# dualHYD-PRESS.net
KiCad netlist of a schematic drawn in EAGLE
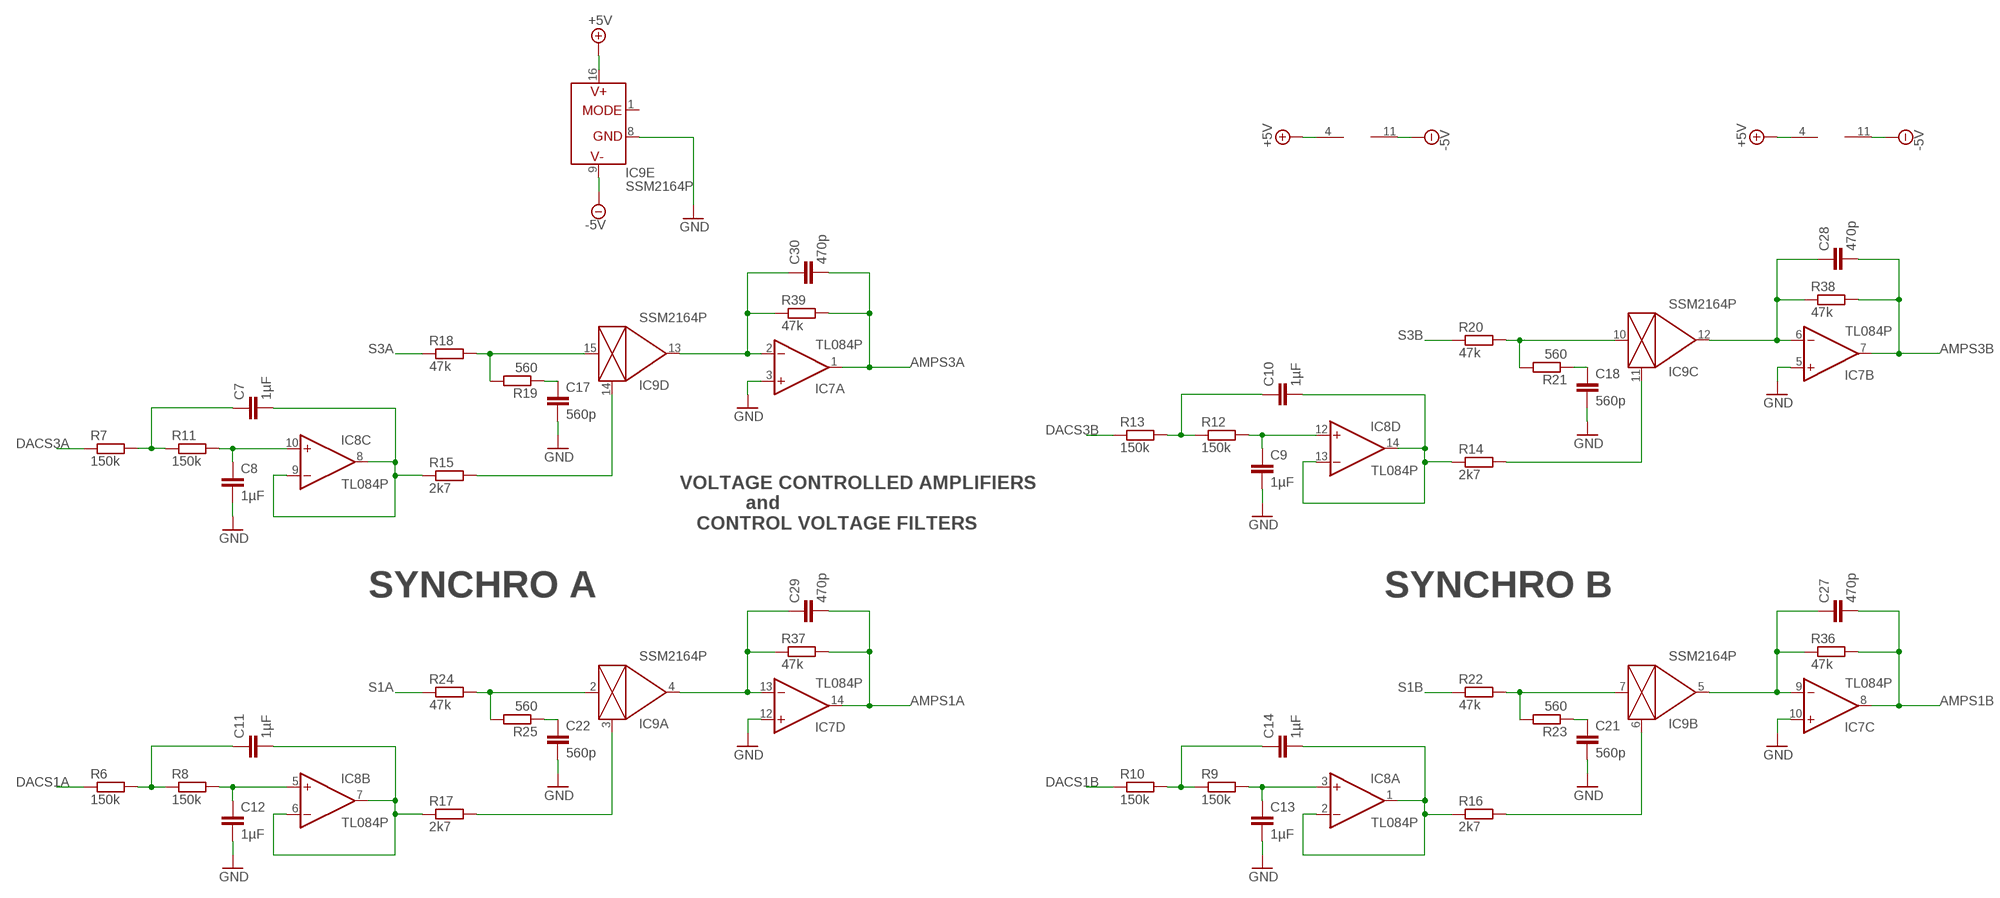
[diagram p0: schematic, sheet 1]
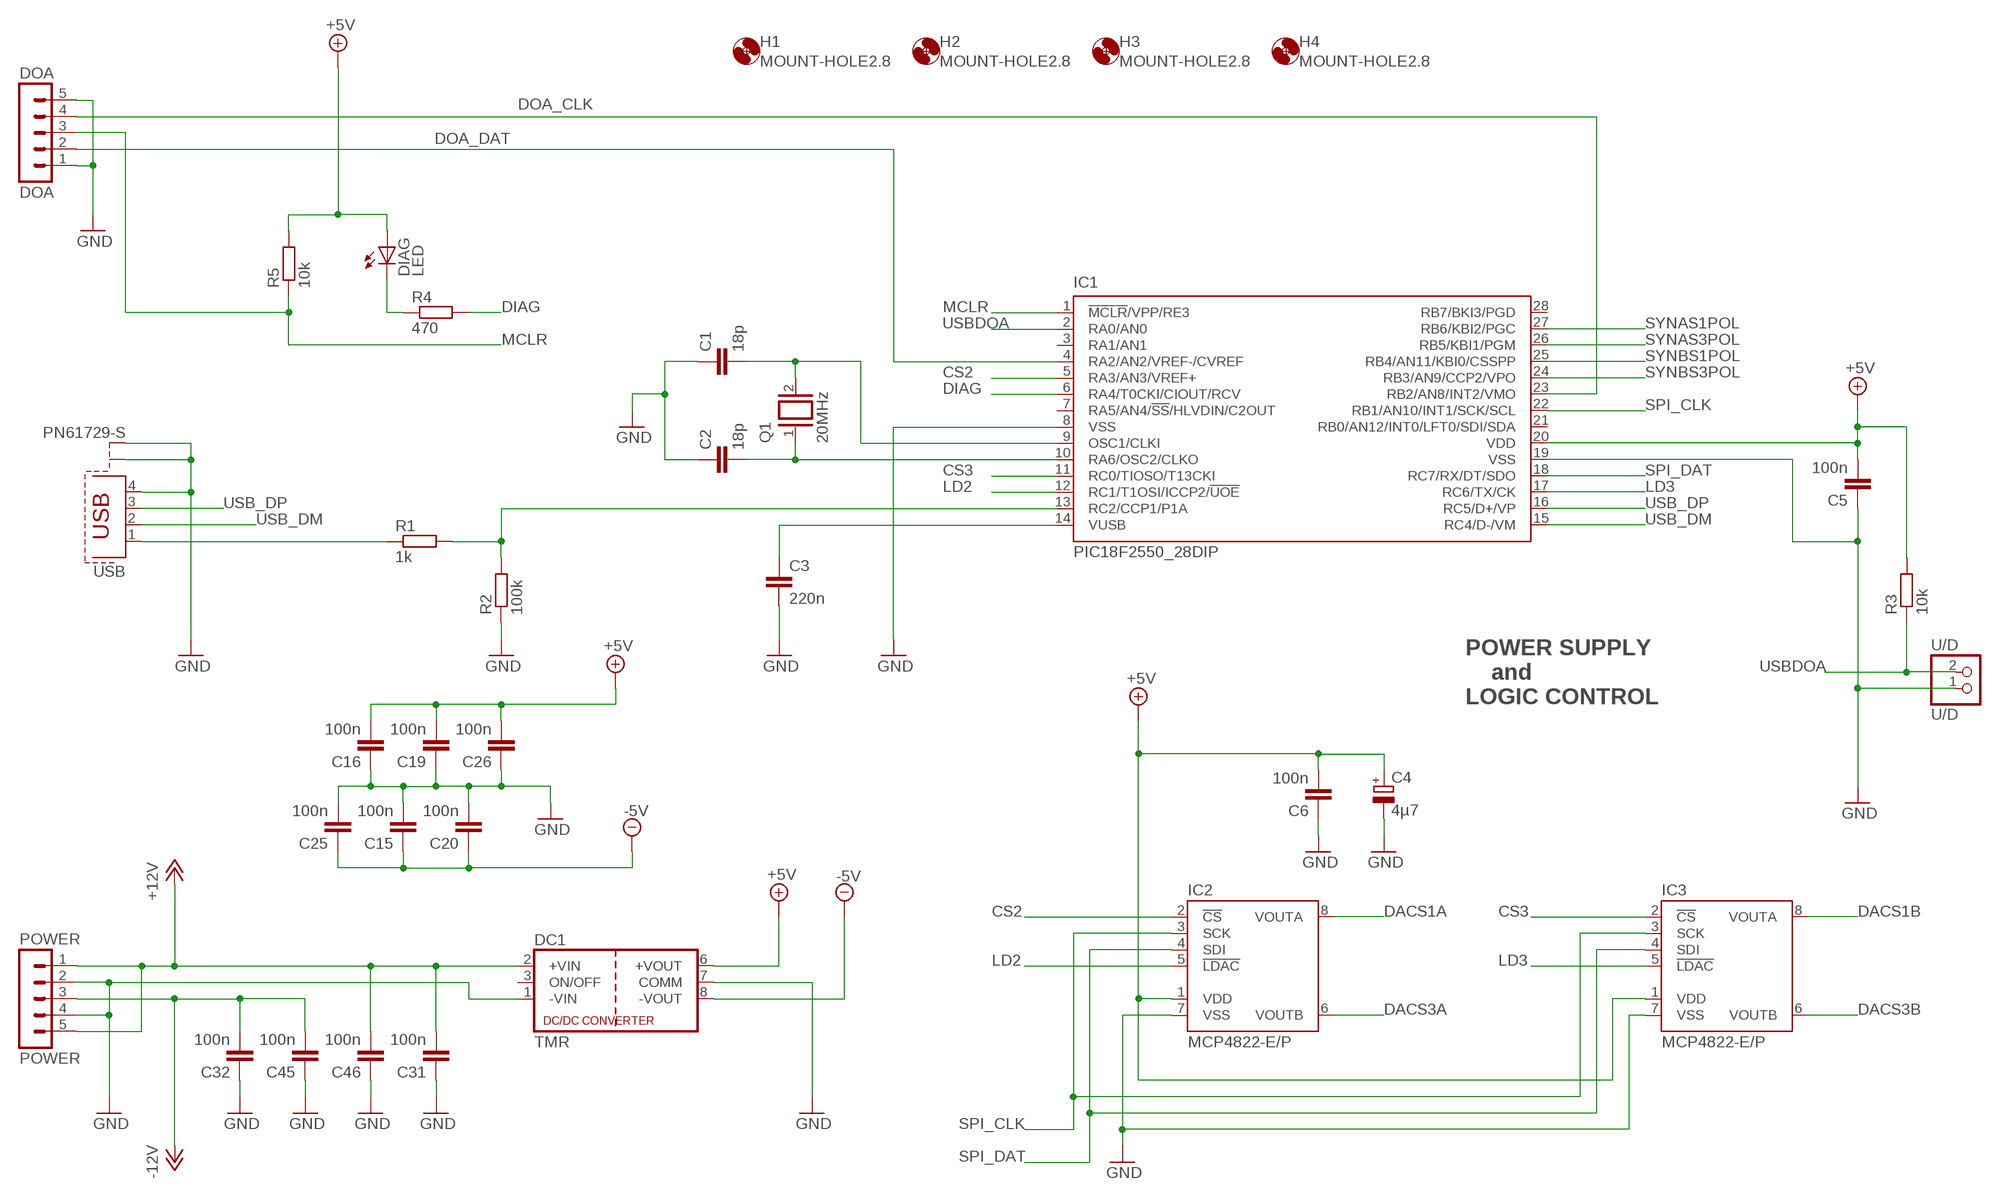
[diagram p1: schematic, sheet 2]
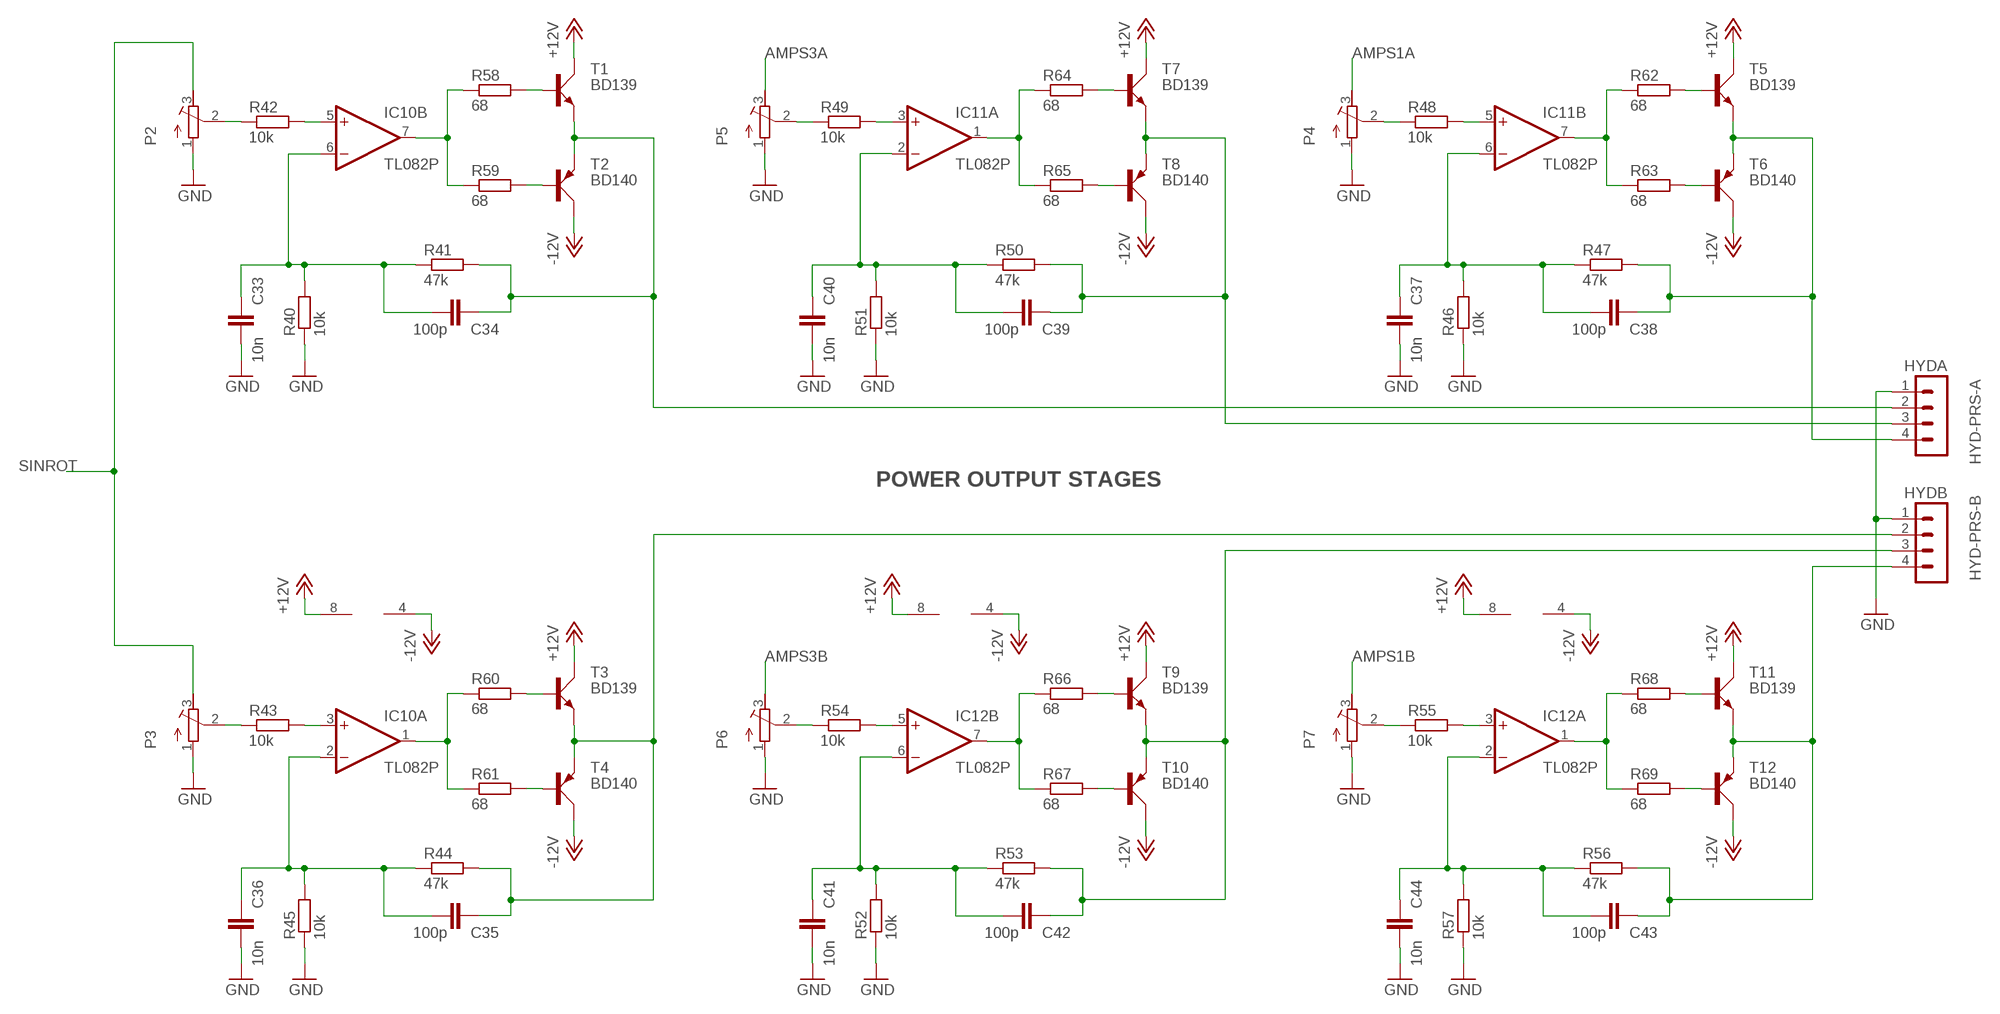
[diagram p2: schematic, sheet 3]
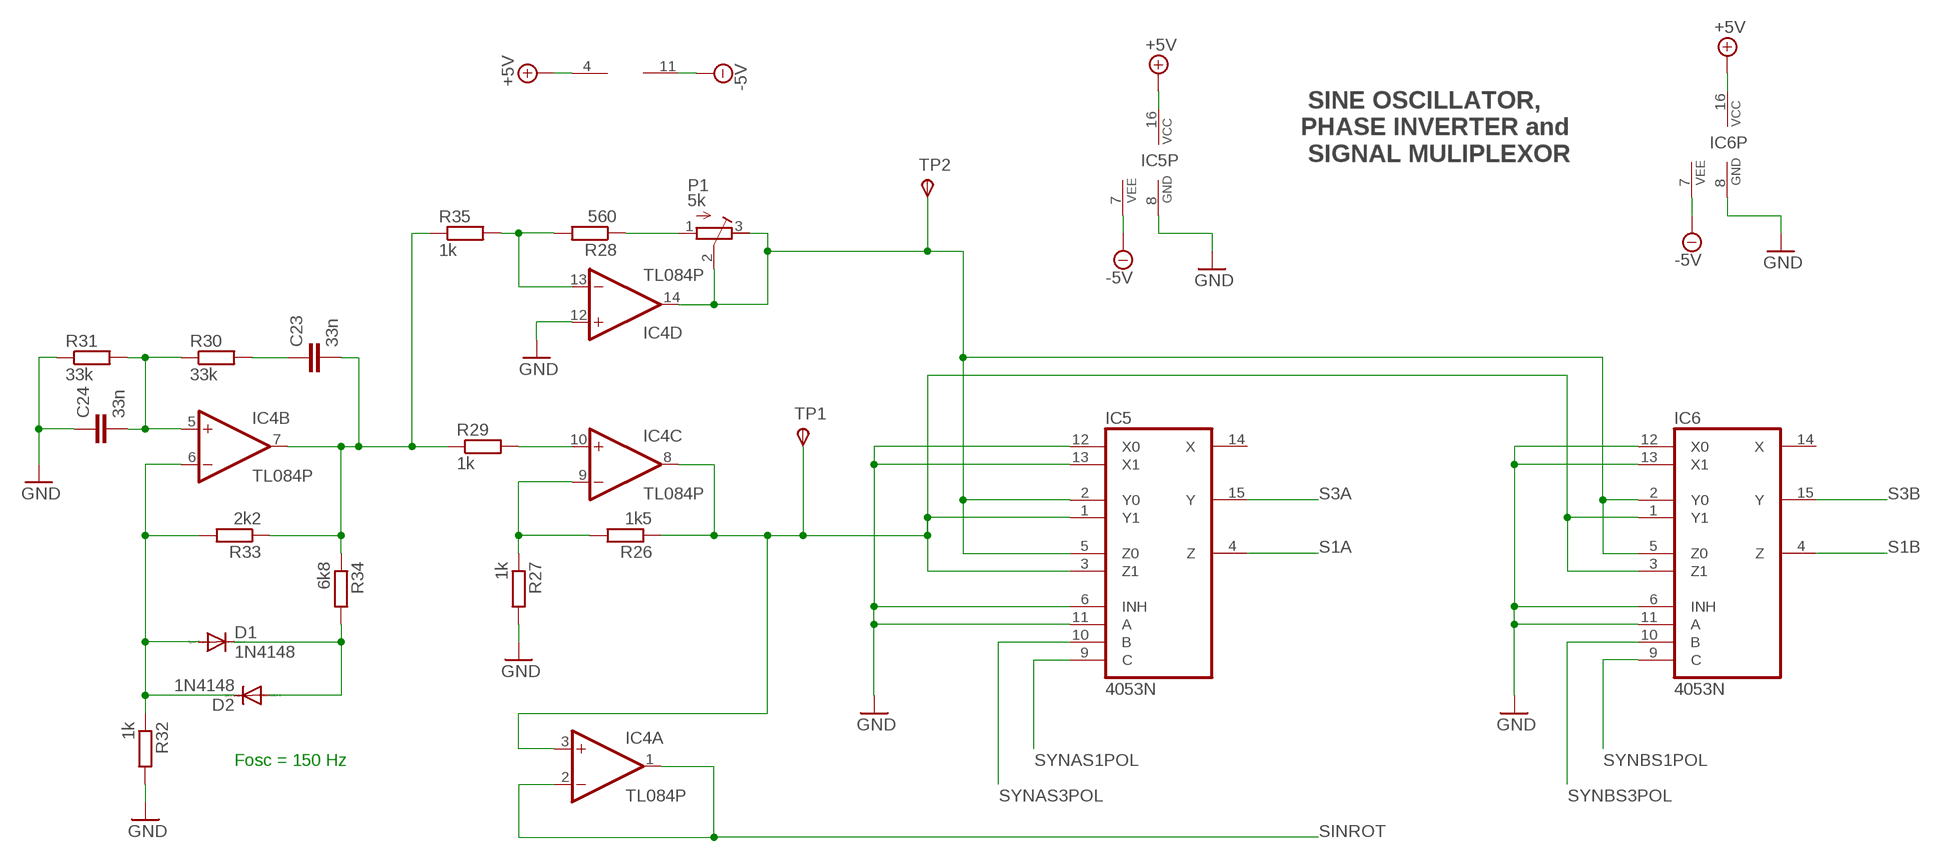
[diagram p3: schematic, sheet 4]

(export (version "E")
  (design (tool "Eeschema 10.0.6"))
  (components
    (comp (ref "C7")
      (value "1µF")
      (footprint "eagle-import:C025-025X050")
      (libsource (lib "eagle-import") (part "C-EU025-025X050"))
    )
    (comp (ref "C8")
      (value "1µF")
      (footprint "eagle-import:C025-025X050")
      (libsource (lib "eagle-import") (part "C-EU025-025X050"))
    )
    (comp (ref "C9")
      (value "1µF")
      (footprint "eagle-import:C025-025X050")
      (libsource (lib "eagle-import") (part "C-EU025-025X050"))
    )
    (comp (ref "C10")
      (value "1µF")
      (footprint "eagle-import:C025-025X050")
      (libsource (lib "eagle-import") (part "C-EU025-025X050"))
    )
    (comp (ref "C11")
      (value "1µF")
      (footprint "eagle-import:C025-025X050")
      (libsource (lib "eagle-import") (part "C-EU025-025X050"))
    )
    (comp (ref "C12")
      (value "1µF")
      (footprint "eagle-import:C025-025X050")
      (libsource (lib "eagle-import") (part "C-EU025-025X050"))
    )
    (comp (ref "C13")
      (value "1µF")
      (footprint "eagle-import:C025-025X050")
      (libsource (lib "eagle-import") (part "C-EU025-025X050"))
    )
    (comp (ref "C14")
      (value "1µF")
      (footprint "eagle-import:C025-025X050")
      (libsource (lib "eagle-import") (part "C-EU025-025X050"))
    )
    (comp (ref "C17")
      (value "560p")
      (footprint "eagle-import:C025-025X050")
      (libsource (lib "eagle-import") (part "C-EU025-025X050"))
    )
    (comp (ref "C18")
      (value "560p")
      (footprint "eagle-import:C025-025X050")
      (libsource (lib "eagle-import") (part "C-EU025-025X050"))
    )
    (comp (ref "C21")
      (value "560p")
      (footprint "eagle-import:C025-025X050")
      (libsource (lib "eagle-import") (part "C-EU025-025X050"))
    )
    (comp (ref "C22")
      (value "560p")
      (footprint "eagle-import:C025-025X050")
      (libsource (lib "eagle-import") (part "C-EU025-025X050"))
    )
    (comp (ref "C27")
      (value "470p")
      (footprint "eagle-import:C025-025X050")
      (libsource (lib "eagle-import") (part "C-EU025-025X050"))
    )
    (comp (ref "C28")
      (value "470p")
      (footprint "eagle-import:C025-025X050")
      (libsource (lib "eagle-import") (part "C-EU025-025X050"))
    )
    (comp (ref "C29")
      (value "470p")
      (footprint "eagle-import:C025-025X050")
      (libsource (lib "eagle-import") (part "C-EU025-025X050"))
    )
    (comp (ref "C30")
      (value "470p")
      (footprint "eagle-import:C025-025X050")
      (libsource (lib "eagle-import") (part "C-EU025-025X050"))
    )
    (comp (ref "IC7")
      (value "TL084P")
      (footprint "eagle-import:DIL14")
      (libsource (lib "eagle-import") (part "TL084P"))
    )
    (comp (ref "IC8")
      (value "TL084P")
      (footprint "eagle-import:DIL14")
      (libsource (lib "eagle-import") (part "TL084P"))
    )
    (comp (ref "IC9")
      (value "SSM2164P")
      (footprint "eagle-import:DIL16")
      (libsource (lib "eagle-import") (part "SSM2164P"))
    )
    (comp (ref "R6")
      (value "150k")
      (footprint "eagle-import:0207_7")
      (libsource (lib "eagle-import") (part "R-EU_0207/7"))
    )
    (comp (ref "R7")
      (value "150k")
      (footprint "eagle-import:0207_7")
      (libsource (lib "eagle-import") (part "R-EU_0207/7"))
    )
    (comp (ref "R8")
      (value "150k")
      (footprint "eagle-import:0207_7")
      (libsource (lib "eagle-import") (part "R-EU_0207/7"))
    )
    (comp (ref "R9")
      (value "150k")
      (footprint "eagle-import:0207_7")
      (libsource (lib "eagle-import") (part "R-EU_0207/7"))
    )
    (comp (ref "R10")
      (value "150k")
      (footprint "eagle-import:0207_7")
      (libsource (lib "eagle-import") (part "R-EU_0207/7"))
    )
    (comp (ref "R11")
      (value "150k")
      (footprint "eagle-import:0207_7")
      (libsource (lib "eagle-import") (part "R-EU_0207/7"))
    )
    (comp (ref "R12")
      (value "150k")
      (footprint "eagle-import:0207_7")
      (libsource (lib "eagle-import") (part "R-EU_0207/7"))
    )
    (comp (ref "R13")
      (value "150k")
      (footprint "eagle-import:0207_7")
      (libsource (lib "eagle-import") (part "R-EU_0207/7"))
    )
    (comp (ref "R14")
      (value "2k7")
      (footprint "eagle-import:0207_7")
      (libsource (lib "eagle-import") (part "R-EU_0207/7"))
    )
    (comp (ref "R15")
      (value "2k7")
      (footprint "eagle-import:0207_7")
      (libsource (lib "eagle-import") (part "R-EU_0207/7"))
    )
    (comp (ref "R16")
      (value "2k7")
      (footprint "eagle-import:0207_7")
      (libsource (lib "eagle-import") (part "R-EU_0207/7"))
    )
    (comp (ref "R17")
      (value "2k7")
      (footprint "eagle-import:0207_7")
      (libsource (lib "eagle-import") (part "R-EU_0207/7"))
    )
    (comp (ref "R18")
      (value "47k")
      (footprint "eagle-import:0207_7")
      (libsource (lib "eagle-import") (part "R-EU_0207/7"))
    )
    (comp (ref "R19")
      (value "560")
      (footprint "eagle-import:0207_7")
      (libsource (lib "eagle-import") (part "R-EU_0207/7"))
    )
    (comp (ref "R20")
      (value "47k")
      (footprint "eagle-import:0207_7")
      (libsource (lib "eagle-import") (part "R-EU_0207/7"))
    )
    (comp (ref "R21")
      (value "560")
      (footprint "eagle-import:0207_7")
      (libsource (lib "eagle-import") (part "R-EU_0207/7"))
    )
    (comp (ref "R22")
      (value "47k")
      (footprint "eagle-import:0207_7")
      (libsource (lib "eagle-import") (part "R-EU_0207/7"))
    )
    (comp (ref "R23")
      (value "560")
      (footprint "eagle-import:0207_7")
      (libsource (lib "eagle-import") (part "R-EU_0207/7"))
    )
    (comp (ref "R24")
      (value "47k")
      (footprint "eagle-import:0207_7")
      (libsource (lib "eagle-import") (part "R-EU_0207/7"))
    )
    (comp (ref "R25")
      (value "560")
      (footprint "eagle-import:0207_7")
      (libsource (lib "eagle-import") (part "R-EU_0207/7"))
    )
    (comp (ref "R36")
      (value "47k")
      (footprint "eagle-import:0207_7")
      (libsource (lib "eagle-import") (part "R-EU_0207/7"))
    )
    (comp (ref "R37")
      (value "47k")
      (footprint "eagle-import:0207_7")
      (libsource (lib "eagle-import") (part "R-EU_0207/7"))
    )
    (comp (ref "R38")
      (value "47k")
      (footprint "eagle-import:0207_7")
      (libsource (lib "eagle-import") (part "R-EU_0207/7"))
    )
    (comp (ref "R39")
      (value "47k")
      (footprint "eagle-import:0207_7")
      (libsource (lib "eagle-import") (part "R-EU_0207/7"))
    )
    (comp (ref "C23")
      (value "33n")
      (footprint "eagle-import:C025-024X044")
      (libsource (lib "eagle-import") (part "C-EU025-024X044"))
    )
    (comp (ref "C24")
      (value "33n")
      (footprint "eagle-import:C025-024X044")
      (libsource (lib "eagle-import") (part "C-EU025-024X044"))
    )
    (comp (ref "D1")
      (value "1N4148")
      (footprint "eagle-import:DO35-7")
      (libsource (lib "eagle-import") (part "1N4148DO35-7"))
    )
    (comp (ref "D2")
      (value "1N4148")
      (footprint "eagle-import:DO35-7")
      (libsource (lib "eagle-import") (part "1N4148DO35-7"))
    )
    (comp (ref "IC4")
      (value "TL084P")
      (footprint "eagle-import:DIL14")
      (libsource (lib "eagle-import") (part "TL084P"))
    )
    (comp (ref "IC5")
      (value "4053N")
      (footprint "eagle-import:DIL16")
      (libsource (lib "eagle-import") (part "4053N"))
    )
    (comp (ref "IC6")
      (value "4053N")
      (footprint "eagle-import:DIL16")
      (libsource (lib "eagle-import") (part "4053N"))
    )
    (comp (ref "P1")
      (value "5k")
      (footprint "eagle-import:RTRIM64Y")
      (libsource (lib "eagle-import") (part "R-TRIMM64Y"))
    )
    (comp (ref "R26")
      (value "1k5")
      (footprint "eagle-import:0204_7")
      (libsource (lib "eagle-import") (part "R-EU_0204/7"))
    )
    (comp (ref "R27")
      (value "1k")
      (footprint "eagle-import:0204_7")
      (libsource (lib "eagle-import") (part "R-EU_0204/7"))
    )
    (comp (ref "R28")
      (value "560")
      (footprint "eagle-import:0204_7")
      (libsource (lib "eagle-import") (part "R-EU_0204/7"))
    )
    (comp (ref "R29")
      (value "1k")
      (footprint "eagle-import:0204_7")
      (libsource (lib "eagle-import") (part "R-EU_0204/7"))
    )
    (comp (ref "R30")
      (value "33k")
      (footprint "eagle-import:0204_7")
      (libsource (lib "eagle-import") (part "R-EU_0204/7"))
    )
    (comp (ref "R31")
      (value "33k")
      (footprint "eagle-import:0204_7")
      (libsource (lib "eagle-import") (part "R-EU_0204/7"))
    )
    (comp (ref "R32")
      (value "1k")
      (footprint "eagle-import:0204_7")
      (libsource (lib "eagle-import") (part "R-EU_0204/7"))
    )
    (comp (ref "R33")
      (value "2k2")
      (footprint "eagle-import:0204_7")
      (libsource (lib "eagle-import") (part "R-EU_0204/7"))
    )
    (comp (ref "R34")
      (value "6k8")
      (footprint "eagle-import:0204_7")
      (libsource (lib "eagle-import") (part "R-EU_0204/7"))
    )
    (comp (ref "R35")
      (value "1k")
      (footprint "eagle-import:0204_7")
      (libsource (lib "eagle-import") (part "R-EU_0204/7"))
    )
    (comp (ref "TP1")
      (value "TPSPAD1-17")
      (footprint "eagle-import:P1-17")
      (libsource (lib "eagle-import") (part "TPSPAD1-17"))
    )
    (comp (ref "TP2")
      (value "TPSPAD1-17")
      (footprint "eagle-import:P1-17")
      (libsource (lib "eagle-import") (part "TPSPAD1-17"))
    )
    (comp (ref "C1")
      (value "18p")
      (footprint "eagle-import:C025-025X050")
      (libsource (lib "eagle-import") (part "C-EU025-025X050"))
    )
    (comp (ref "C2")
      (value "18p")
      (footprint "eagle-import:C025-025X050")
      (libsource (lib "eagle-import") (part "C-EU025-025X050"))
    )
    (comp (ref "C3")
      (value "220n")
      (footprint "eagle-import:C5B3")
      (libsource (lib "eagle-import") (part "C5/3"))
    )
    (comp (ref "C4")
      (value "4µ7")
      (footprint "eagle-import:E2,5-5")
      (libsource (lib "eagle-import") (part "CPOL-EUE2.5-5"))
    )
    (comp (ref "C5")
      (value "100n")
      (footprint "eagle-import:C025-025X050")
      (libsource (lib "eagle-import") (part "C-EU025-025X050"))
    )
    (comp (ref "C6")
      (value "100n")
      (footprint "eagle-import:C025-025X050")
      (libsource (lib "eagle-import") (part "C-EU025-025X050"))
    )
    (comp (ref "C15")
      (value "100n")
      (footprint "eagle-import:C025-025X050")
      (libsource (lib "eagle-import") (part "C-EU025-025X050"))
    )
    (comp (ref "C16")
      (value "100n")
      (footprint "eagle-import:C025-025X050")
      (libsource (lib "eagle-import") (part "C-EU025-025X050"))
    )
    (comp (ref "C19")
      (value "100n")
      (footprint "eagle-import:C025-025X050")
      (libsource (lib "eagle-import") (part "C-EU025-025X050"))
    )
    (comp (ref "C20")
      (value "100n")
      (footprint "eagle-import:C025-025X050")
      (libsource (lib "eagle-import") (part "C-EU025-025X050"))
    )
    (comp (ref "C25")
      (value "100n")
      (footprint "eagle-import:C025-025X050")
      (libsource (lib "eagle-import") (part "C-EU025-025X050"))
    )
    (comp (ref "C26")
      (value "100n")
      (footprint "eagle-import:C025-025X050")
      (libsource (lib "eagle-import") (part "C-EU025-025X050"))
    )
    (comp (ref "C31")
      (value "100n")
      (footprint "eagle-import:C025-025X050")
      (libsource (lib "eagle-import") (part "C-EU025-025X050"))
    )
    (comp (ref "C32")
      (value "100n")
      (footprint "eagle-import:C025-025X050")
      (libsource (lib "eagle-import") (part "C-EU025-025X050"))
    )
    (comp (ref "C45")
      (value "100n")
      (footprint "eagle-import:C025-025X050")
      (libsource (lib "eagle-import") (part "C-EU025-025X050"))
    )
    (comp (ref "C46")
      (value "100n")
      (footprint "eagle-import:C025-025X050")
      (libsource (lib "eagle-import") (part "C-EU025-025X050"))
    )
    (comp (ref "DC1")
      (value "TMR")
      (footprint "eagle-import:TRACO_SIP-8")
      (libsource (lib "eagle-import") (part "TMR"))
    )
    (comp (ref "DIAG")
      (value "LED")
      (footprint "eagle-import:LED3MM")
      (libsource (lib "eagle-import") (part "LED3MM"))
    )
    (comp (ref "DOA")
      (value "DOA")
      (footprint "eagle-import:MA05-1")
      (libsource (lib "eagle-import") (part "MA05-1"))
    )
    (comp (ref "H1")
      (value "MOUNT-HOLE2.8")
      (footprint "eagle-import:2,8")
      (libsource (lib "eagle-import") (part "MOUNT-HOLE2.8"))
    )
    (comp (ref "H2")
      (value "MOUNT-HOLE2.8")
      (footprint "eagle-import:2,8")
      (libsource (lib "eagle-import") (part "MOUNT-HOLE2.8"))
    )
    (comp (ref "H3")
      (value "MOUNT-HOLE2.8")
      (footprint "eagle-import:2,8")
      (libsource (lib "eagle-import") (part "MOUNT-HOLE2.8"))
    )
    (comp (ref "H4")
      (value "MOUNT-HOLE2.8")
      (footprint "eagle-import:2,8")
      (libsource (lib "eagle-import") (part "MOUNT-HOLE2.8"))
    )
    (comp (ref "IC1")
      (value "PIC18F2550_28DIP")
      (footprint "eagle-import:DIL28-3")
      (fields (field (name "MF") "MICROCHIP") (field (name "MPN") "PIC18F2550-I/SP"))
      (libsource (lib "eagle-import") (part "PIC18F2_28DIP550"))
    )
    (comp (ref "IC2")
      (value "MCP4822-E/P")
      (footprint "eagle-import:DIL08")
      (libsource (lib "eagle-import") (part "MCP4822-E/P"))
    )
    (comp (ref "IC3")
      (value "MCP4822-E/P")
      (footprint "eagle-import:DIL08")
      (libsource (lib "eagle-import") (part "MCP4822-E/P"))
    )
    (comp (ref "POWER")
      (value "POWER")
      (footprint "eagle-import:MA05-1")
      (libsource (lib "eagle-import") (part "MA05-1"))
    )
    (comp (ref "Q1")
      (value "20MHz")
      (footprint "eagle-import:QS")
      (libsource (lib "eagle-import") (part "XTAL/S"))
    )
    (comp (ref "R1")
      (value "1k")
      (footprint "eagle-import:0204_7")
      (libsource (lib "eagle-import") (part "R-EU_0204/7"))
    )
    (comp (ref "R2")
      (value "100k")
      (footprint "eagle-import:0204_7")
      (libsource (lib "eagle-import") (part "R-EU_0204/7"))
    )
    (comp (ref "R3")
      (value "10k")
      (footprint "eagle-import:0204_7")
      (libsource (lib "eagle-import") (part "R-EU_0204/7"))
    )
    (comp (ref "R4")
      (value "470")
      (footprint "eagle-import:0204_7")
      (libsource (lib "eagle-import") (part "R-EU_0204/7"))
    )
    (comp (ref "R5")
      (value "10k")
      (footprint "eagle-import:0204_7")
      (libsource (lib "eagle-import") (part "R-EU_0204/7"))
    )
    (comp (ref "U/D")
      (value "U/D")
      (footprint "eagle-import:1X02")
      (libsource (lib "eagle-import") (part "PINHD-1X2"))
    )
    (comp (ref "USB")
      (value "PN61729-S")
      (footprint "eagle-import:PN61729-S")
      (libsource (lib "eagle-import") (part "PN61729-S"))
    )
    (comp (ref "C33")
      (value "10n")
      (footprint "eagle-import:C025-025X050")
      (libsource (lib "eagle-import") (part "C-EU025-025X050"))
    )
    (comp (ref "C34")
      (value "100p")
      (footprint "eagle-import:C025-025X050")
      (libsource (lib "eagle-import") (part "C-EU025-025X050"))
    )
    (comp (ref "C35")
      (value "100p")
      (footprint "eagle-import:C025-025X050")
      (libsource (lib "eagle-import") (part "C-EU025-025X050"))
    )
    (comp (ref "C36")
      (value "10n")
      (footprint "eagle-import:C025-025X050")
      (libsource (lib "eagle-import") (part "C-EU025-025X050"))
    )
    (comp (ref "C37")
      (value "10n")
      (footprint "eagle-import:C025-025X050")
      (libsource (lib "eagle-import") (part "C-EU025-025X050"))
    )
    (comp (ref "C38")
      (value "100p")
      (footprint "eagle-import:C025-025X050")
      (libsource (lib "eagle-import") (part "C-EU025-025X050"))
    )
    (comp (ref "C39")
      (value "100p")
      (footprint "eagle-import:C025-025X050")
      (libsource (lib "eagle-import") (part "C-EU025-025X050"))
    )
    (comp (ref "C40")
      (value "10n")
      (footprint "eagle-import:C025-025X050")
      (libsource (lib "eagle-import") (part "C-EU025-025X050"))
    )
    (comp (ref "C41")
      (value "10n")
      (footprint "eagle-import:C025-025X050")
      (libsource (lib "eagle-import") (part "C-EU025-025X050"))
    )
    (comp (ref "C42")
      (value "100p")
      (footprint "eagle-import:C025-025X050")
      (libsource (lib "eagle-import") (part "C-EU025-025X050"))
    )
    (comp (ref "C43")
      (value "100p")
      (footprint "eagle-import:C025-025X050")
      (libsource (lib "eagle-import") (part "C-EU025-025X050"))
    )
    (comp (ref "C44")
      (value "10n")
      (footprint "eagle-import:C025-025X050")
      (libsource (lib "eagle-import") (part "C-EU025-025X050"))
    )
    (comp (ref "HYD-PRS-A")
      (value "HYDA")
      (footprint "eagle-import:MA04-1")
      (libsource (lib "eagle-import") (part "MA04-1"))
    )
    (comp (ref "HYD-PRS-B")
      (value "HYDB")
      (footprint "eagle-import:MA04-1")
      (libsource (lib "eagle-import") (part "MA04-1"))
    )
    (comp (ref "IC10")
      (value "TL082P")
      (footprint "eagle-import:DIL08")
      (libsource (lib "eagle-import") (part "TL082P"))
    )
    (comp (ref "IC11")
      (value "TL082P")
      (footprint "eagle-import:DIL08")
      (libsource (lib "eagle-import") (part "TL082P"))
    )
    (comp (ref "IC12")
      (value "TL082P")
      (footprint "eagle-import:DIL08")
      (libsource (lib "eagle-import") (part "TL082P"))
    )
    (comp (ref "P2")
      (value "R-TRIMM64Y")
      (footprint "eagle-import:RTRIM64Y")
      (libsource (lib "eagle-import") (part "R-TRIMM64Y"))
    )
    (comp (ref "P3")
      (value "R-TRIMM64Y")
      (footprint "eagle-import:RTRIM64Y")
      (libsource (lib "eagle-import") (part "R-TRIMM64Y"))
    )
    (comp (ref "P4")
      (value "R-TRIMM64Y")
      (footprint "eagle-import:RTRIM64Y")
      (libsource (lib "eagle-import") (part "R-TRIMM64Y"))
    )
    (comp (ref "P5")
      (value "R-TRIMM64Y")
      (footprint "eagle-import:RTRIM64Y")
      (libsource (lib "eagle-import") (part "R-TRIMM64Y"))
    )
    (comp (ref "P6")
      (value "R-TRIMM64Y")
      (footprint "eagle-import:RTRIM64Y")
      (libsource (lib "eagle-import") (part "R-TRIMM64Y"))
    )
    (comp (ref "P7")
      (value "R-TRIMM64Y")
      (footprint "eagle-import:RTRIM64Y")
      (libsource (lib "eagle-import") (part "R-TRIMM64Y"))
    )
    (comp (ref "R40")
      (value "10k")
      (footprint "eagle-import:0204_7")
      (libsource (lib "eagle-import") (part "R-EU_0204/7"))
    )
    (comp (ref "R41")
      (value "47k")
      (footprint "eagle-import:0204_7")
      (libsource (lib "eagle-import") (part "R-EU_0204/7"))
    )
    (comp (ref "R42")
      (value "10k")
      (footprint "eagle-import:0204_7")
      (libsource (lib "eagle-import") (part "R-EU_0204/7"))
    )
    (comp (ref "R43")
      (value "10k")
      (footprint "eagle-import:0204_7")
      (libsource (lib "eagle-import") (part "R-EU_0204/7"))
    )
    (comp (ref "R44")
      (value "47k")
      (footprint "eagle-import:0204_7")
      (libsource (lib "eagle-import") (part "R-EU_0204/7"))
    )
    (comp (ref "R45")
      (value "10k")
      (footprint "eagle-import:0204_7")
      (libsource (lib "eagle-import") (part "R-EU_0204/7"))
    )
    (comp (ref "R46")
      (value "10k")
      (footprint "eagle-import:0204_7")
      (libsource (lib "eagle-import") (part "R-EU_0204/7"))
    )
    (comp (ref "R47")
      (value "47k")
      (footprint "eagle-import:0204_7")
      (libsource (lib "eagle-import") (part "R-EU_0204/7"))
    )
    (comp (ref "R48")
      (value "10k")
      (footprint "eagle-import:0204_7")
      (libsource (lib "eagle-import") (part "R-EU_0204/7"))
    )
    (comp (ref "R49")
      (value "10k")
      (footprint "eagle-import:0204_7")
      (libsource (lib "eagle-import") (part "R-EU_0204/7"))
    )
    (comp (ref "R50")
      (value "47k")
      (footprint "eagle-import:0204_7")
      (libsource (lib "eagle-import") (part "R-EU_0204/7"))
    )
    (comp (ref "R51")
      (value "10k")
      (footprint "eagle-import:0204_7")
      (libsource (lib "eagle-import") (part "R-EU_0204/7"))
    )
    (comp (ref "R52")
      (value "10k")
      (footprint "eagle-import:0204_7")
      (libsource (lib "eagle-import") (part "R-EU_0204/7"))
    )
    (comp (ref "R53")
      (value "47k")
      (footprint "eagle-import:0204_7")
      (libsource (lib "eagle-import") (part "R-EU_0204/7"))
    )
    (comp (ref "R54")
      (value "10k")
      (footprint "eagle-import:0204_7")
      (libsource (lib "eagle-import") (part "R-EU_0204/7"))
    )
    (comp (ref "R55")
      (value "10k")
      (footprint "eagle-import:0204_7")
      (libsource (lib "eagle-import") (part "R-EU_0204/7"))
    )
    (comp (ref "R56")
      (value "47k")
      (footprint "eagle-import:0204_7")
      (libsource (lib "eagle-import") (part "R-EU_0204/7"))
    )
    (comp (ref "R57")
      (value "10k")
      (footprint "eagle-import:0204_7")
      (libsource (lib "eagle-import") (part "R-EU_0204/7"))
    )
    (comp (ref "R58")
      (value "68")
      (footprint "eagle-import:0204_7")
      (libsource (lib "eagle-import") (part "R-EU_0204/7"))
    )
    (comp (ref "R59")
      (value "68")
      (footprint "eagle-import:0204_7")
      (libsource (lib "eagle-import") (part "R-EU_0204/7"))
    )
    (comp (ref "R60")
      (value "68")
      (footprint "eagle-import:0204_7")
      (libsource (lib "eagle-import") (part "R-EU_0204/7"))
    )
    (comp (ref "R61")
      (value "68")
      (footprint "eagle-import:0204_7")
      (libsource (lib "eagle-import") (part "R-EU_0204/7"))
    )
    (comp (ref "R62")
      (value "68")
      (footprint "eagle-import:0204_7")
      (libsource (lib "eagle-import") (part "R-EU_0204/7"))
    )
    (comp (ref "R63")
      (value "68")
      (footprint "eagle-import:0204_7")
      (libsource (lib "eagle-import") (part "R-EU_0204/7"))
    )
    (comp (ref "R64")
      (value "68")
      (footprint "eagle-import:0204_7")
      (libsource (lib "eagle-import") (part "R-EU_0204/7"))
    )
    (comp (ref "R65")
      (value "68")
      (footprint "eagle-import:0204_7")
      (libsource (lib "eagle-import") (part "R-EU_0204/7"))
    )
    (comp (ref "R66")
      (value "68")
      (footprint "eagle-import:0204_7")
      (libsource (lib "eagle-import") (part "R-EU_0204/7"))
    )
    (comp (ref "R67")
      (value "68")
      (footprint "eagle-import:0204_7")
      (libsource (lib "eagle-import") (part "R-EU_0204/7"))
    )
    (comp (ref "R68")
      (value "68")
      (footprint "eagle-import:0204_7")
      (libsource (lib "eagle-import") (part "R-EU_0204/7"))
    )
    (comp (ref "R69")
      (value "68")
      (footprint "eagle-import:0204_7")
      (libsource (lib "eagle-import") (part "R-EU_0204/7"))
    )
    (comp (ref "T1")
      (value "BD139")
      (footprint "eagle-import:TO126AV")
      (libsource (lib "eagle-import") (part "BD139"))
    )
    (comp (ref "T2")
      (value "BD140")
      (footprint "eagle-import:TO126AV")
      (libsource (lib "eagle-import") (part "BD140"))
    )
    (comp (ref "T3")
      (value "BD139")
      (footprint "eagle-import:TO126AV")
      (libsource (lib "eagle-import") (part "BD139"))
    )
    (comp (ref "T4")
      (value "BD140")
      (footprint "eagle-import:TO126AV")
      (libsource (lib "eagle-import") (part "BD140"))
    )
    (comp (ref "T5")
      (value "BD139")
      (footprint "eagle-import:TO126AV")
      (libsource (lib "eagle-import") (part "BD139"))
    )
    (comp (ref "T6")
      (value "BD140")
      (footprint "eagle-import:TO126AV")
      (libsource (lib "eagle-import") (part "BD140"))
    )
    (comp (ref "T7")
      (value "BD139")
      (footprint "eagle-import:TO126AV")
      (libsource (lib "eagle-import") (part "BD139"))
    )
    (comp (ref "T8")
      (value "BD140")
      (footprint "eagle-import:TO126AV")
      (libsource (lib "eagle-import") (part "BD140"))
    )
    (comp (ref "T9")
      (value "BD139")
      (footprint "eagle-import:TO126AV")
      (libsource (lib "eagle-import") (part "BD139"))
    )
    (comp (ref "T10")
      (value "BD140")
      (footprint "eagle-import:TO126AV")
      (libsource (lib "eagle-import") (part "BD140"))
    )
    (comp (ref "T11")
      (value "BD139")
      (footprint "eagle-import:TO126AV")
      (libsource (lib "eagle-import") (part "BD139"))
    )
    (comp (ref "T12")
      (value "BD140")
      (footprint "eagle-import:TO126AV")
      (libsource (lib "eagle-import") (part "BD140"))
    )
  )
  (nets
    (net (code "1") (name "+5V") (class "Default")
      (node (ref "C16") (pin "2") (pinfunction "2_2") (pintype "passive"))
      (node (ref "C19") (pin "2") (pinfunction "2_2") (pintype "passive"))
      (node (ref "C26") (pin "2") (pinfunction "2_2") (pintype "passive"))
      (node (ref "C4") (pin "+") (pinfunction "+_+") (pintype "passive"))
      (node (ref "C5") (pin "2") (pinfunction "2_2") (pintype "passive"))
      (node (ref "C6") (pin "2") (pinfunction "2_2") (pintype "passive"))
      (node (ref "DC1") (pin "6") (pinfunction "+VOUT_6") (pintype "passive"))
      (node (ref "DIAG") (pin "A") (pinfunction "A_A") (pintype "passive"))
      (node (ref "IC1") (pin "20") (pinfunction "VDD_20") (pintype "power_in"))
      (node (ref "IC2") (pin "1") (pinfunction "VDD_1") (pintype "power_in"))
      (node (ref "IC3") (pin "1") (pinfunction "VDD_1") (pintype "power_in"))
      (node (ref "IC4") (pin "4") (pinfunction "V+_4") (pintype "power_in"))
      (node (ref "IC5") (pin "16") (pinfunction "VCC_16") (pintype "power_in"))
      (node (ref "IC6") (pin "16") (pinfunction "VCC_16") (pintype "power_in"))
      (node (ref "IC7") (pin "4") (pinfunction "V+_4") (pintype "power_in"))
      (node (ref "IC8") (pin "4") (pinfunction "V+_4") (pintype "power_in"))
      (node (ref "IC9") (pin "16") (pinfunction "V+_16") (pintype "power_in"))
      (node (ref "R3") (pin "2") (pinfunction "2_2") (pintype "passive"))
      (node (ref "R5") (pin "2") (pinfunction "2_2") (pintype "passive"))
    )
    (net (code "2") (name "+12V") (class "Default")
      (node (ref "C31") (pin "2") (pinfunction "2_2") (pintype "passive"))
      (node (ref "C46") (pin "2") (pinfunction "2_2") (pintype "passive"))
      (node (ref "DC1") (pin "2") (pinfunction "+VIN_2") (pintype "passive"))
      (node (ref "IC10") (pin "8") (pinfunction "V+_8") (pintype "power_in"))
      (node (ref "IC11") (pin "8") (pinfunction "V+_8") (pintype "power_in"))
      (node (ref "IC12") (pin "8") (pinfunction "V+_8") (pintype "power_in"))
      (node (ref "POWER") (pin "1") (pinfunction "1_1") (pintype "passive"))
      (node (ref "POWER") (pin "5") (pinfunction "5_5") (pintype "passive"))
      (node (ref "T1") (pin "C") (pinfunction "C_C") (pintype "passive"))
      (node (ref "T11") (pin "C") (pinfunction "C_C") (pintype "passive"))
      (node (ref "T3") (pin "C") (pinfunction "C_C") (pintype "passive"))
      (node (ref "T5") (pin "C") (pinfunction "C_C") (pintype "passive"))
      (node (ref "T7") (pin "C") (pinfunction "C_C") (pintype "passive"))
      (node (ref "T9") (pin "C") (pinfunction "C_C") (pintype "passive"))
    )
    (net (code "3") (name "-5V") (class "Default")
      (node (ref "C15") (pin "1") (pinfunction "1_1") (pintype "passive"))
      (node (ref "C20") (pin "1") (pinfunction "1_1") (pintype "passive"))
      (node (ref "C25") (pin "1") (pinfunction "1_1") (pintype "passive"))
      (node (ref "DC1") (pin "8") (pinfunction "-VOUT_8") (pintype "passive"))
      (node (ref "IC4") (pin "11") (pinfunction "V-_11") (pintype "power_in"))
      (node (ref "IC5") (pin "7") (pinfunction "VEE_7") (pintype "power_in"))
      (node (ref "IC6") (pin "7") (pinfunction "VEE_7") (pintype "power_in"))
      (node (ref "IC7") (pin "11") (pinfunction "V-_11") (pintype "power_in"))
      (node (ref "IC8") (pin "11") (pinfunction "V-_11") (pintype "power_in"))
      (node (ref "IC9") (pin "9") (pinfunction "V-_9") (pintype "power_in"))
    )
    (net (code "4") (name "-12V") (class "Default")
      (node (ref "C32") (pin "2") (pinfunction "2_2") (pintype "passive"))
      (node (ref "C45") (pin "2") (pinfunction "2_2") (pintype "passive"))
      (node (ref "IC10") (pin "4") (pinfunction "V-_4") (pintype "power_in"))
      (node (ref "IC11") (pin "4") (pinfunction "V-_4") (pintype "power_in"))
      (node (ref "IC12") (pin "4") (pinfunction "V-_4") (pintype "power_in"))
      (node (ref "POWER") (pin "3") (pinfunction "3_3") (pintype "passive"))
      (node (ref "T10") (pin "C") (pinfunction "C_C") (pintype "passive"))
      (node (ref "T12") (pin "C") (pinfunction "C_C") (pintype "passive"))
      (node (ref "T2") (pin "C") (pinfunction "C_C") (pintype "passive"))
      (node (ref "T4") (pin "C") (pinfunction "C_C") (pintype "passive"))
      (node (ref "T6") (pin "C") (pinfunction "C_C") (pintype "passive"))
      (node (ref "T8") (pin "C") (pinfunction "C_C") (pintype "passive"))
    )
    (net (code "5") (name "AMPS1A") (class "Default")
      (node (ref "C29") (pin "2") (pinfunction "2_2") (pintype "passive"))
      (node (ref "IC7") (pin "14") (pinfunction "OUT_14") (pintype "output"))
      (node (ref "P4") (pin "3") (pinfunction "E_3") (pintype "passive"))
      (node (ref "R37") (pin "2") (pinfunction "2_2") (pintype "passive"))
    )
    (net (code "6") (name "AMPS1B") (class "Default")
      (node (ref "C27") (pin "2") (pinfunction "2_2") (pintype "passive"))
      (node (ref "IC7") (pin "8") (pinfunction "OUT_8") (pintype "output"))
      (node (ref "P7") (pin "3") (pinfunction "E_3") (pintype "passive"))
      (node (ref "R36") (pin "2") (pinfunction "2_2") (pintype "passive"))
    )
    (net (code "7") (name "AMPS3A") (class "Default")
      (node (ref "C30") (pin "2") (pinfunction "2_2") (pintype "passive"))
      (node (ref "IC7") (pin "1") (pinfunction "OUT_1") (pintype "output"))
      (node (ref "P5") (pin "3") (pinfunction "E_3") (pintype "passive"))
      (node (ref "R39") (pin "2") (pinfunction "2_2") (pintype "passive"))
    )
    (net (code "8") (name "AMPS3B") (class "Default")
      (node (ref "C28") (pin "2") (pinfunction "2_2") (pintype "passive"))
      (node (ref "IC7") (pin "7") (pinfunction "OUT_7") (pintype "output"))
      (node (ref "P6") (pin "3") (pinfunction "E_3") (pintype "passive"))
      (node (ref "R38") (pin "2") (pinfunction "2_2") (pintype "passive"))
    )
    (net (code "9") (name "CS2") (class "Default")
      (node (ref "IC1") (pin "5") (pinfunction "RA3/AN3/VREF+_5") (pintype "bidirectional"))
      (node (ref "IC2") (pin "2") (pinfunction "~{CS}_2") (pintype "input"))
    )
    (net (code "10") (name "CS3") (class "Default")
      (node (ref "IC1") (pin "11") (pinfunction "RC0/TIOSO/T13CKI_11") (pintype "bidirectional"))
      (node (ref "IC3") (pin "2") (pinfunction "~{CS}_2") (pintype "input"))
    )
    (net (code "11") (name "DACS1A") (class "Default")
      (node (ref "IC2") (pin "8") (pinfunction "VOUTA_8") (pintype "output"))
      (node (ref "R6") (pin "1") (pinfunction "1_1") (pintype "passive"))
    )
    (net (code "12") (name "DACS1B") (class "Default")
      (node (ref "IC3") (pin "8") (pinfunction "VOUTA_8") (pintype "output"))
      (node (ref "R10") (pin "1") (pinfunction "1_1") (pintype "passive"))
    )
    (net (code "13") (name "DACS3A") (class "Default")
      (node (ref "IC2") (pin "6") (pinfunction "VOUTB_6") (pintype "output"))
      (node (ref "R7") (pin "1") (pinfunction "1_1") (pintype "passive"))
    )
    (net (code "14") (name "DACS3B") (class "Default")
      (node (ref "IC3") (pin "6") (pinfunction "VOUTB_6") (pintype "output"))
      (node (ref "R13") (pin "1") (pinfunction "1_1") (pintype "passive"))
    )
    (net (code "15") (name "DIAG") (class "Default")
      (node (ref "IC1") (pin "6") (pinfunction "RA4/T0CKI/CIOUT/RCV_6") (pintype "bidirectional"))
      (node (ref "R4") (pin "2") (pinfunction "2_2") (pintype "passive"))
    )
    (net (code "16") (name "DOA_CLK") (class "Default")
      (node (ref "DOA") (pin "4") (pinfunction "4_4") (pintype "passive"))
      (node (ref "IC1") (pin "23") (pinfunction "RB2/AN8/INT2/VMO_23") (pintype "bidirectional"))
    )
    (net (code "17") (name "DOA_DAT") (class "Default")
      (node (ref "DOA") (pin "2") (pinfunction "2_2") (pintype "passive"))
      (node (ref "IC1") (pin "4") (pinfunction "RA2/AN2/VREF-/CVREF_4") (pintype "bidirectional"))
    )
    (net (code "18") (name "GND") (class "Default")
      (node (ref "C1") (pin "1") (pinfunction "1_1") (pintype "passive"))
      (node (ref "C12") (pin "2") (pinfunction "2_2") (pintype "passive"))
      (node (ref "C13") (pin "2") (pinfunction "2_2") (pintype "passive"))
      (node (ref "C15") (pin "2") (pinfunction "2_2") (pintype "passive"))
      (node (ref "C16") (pin "1") (pinfunction "1_1") (pintype "passive"))
      (node (ref "C17") (pin "2") (pinfunction "2_2") (pintype "passive"))
      (node (ref "C18") (pin "2") (pinfunction "2_2") (pintype "passive"))
      (node (ref "C19") (pin "1") (pinfunction "1_1") (pintype "passive"))
      (node (ref "C2") (pin "1") (pinfunction "1_1") (pintype "passive"))
      (node (ref "C20") (pin "2") (pinfunction "2_2") (pintype "passive"))
      (node (ref "C21") (pin "2") (pinfunction "2_2") (pintype "passive"))
      (node (ref "C22") (pin "2") (pinfunction "2_2") (pintype "passive"))
      (node (ref "C24") (pin "1") (pinfunction "1_1") (pintype "passive"))
      (node (ref "C25") (pin "2") (pinfunction "2_2") (pintype "passive"))
      (node (ref "C26") (pin "1") (pinfunction "1_1") (pintype "passive"))
      (node (ref "C3") (pin "2") (pinfunction "2_2") (pintype "passive"))
      (node (ref "C31") (pin "1") (pinfunction "1_1") (pintype "passive"))
      (node (ref "C32") (pin "1") (pinfunction "1_1") (pintype "passive"))
      (node (ref "C33") (pin "1") (pinfunction "1_1") (pintype "passive"))
      (node (ref "C36") (pin "1") (pinfunction "1_1") (pintype "passive"))
      (node (ref "C37") (pin "1") (pinfunction "1_1") (pintype "passive"))
      (node (ref "C4") (pin "-") (pinfunction "-_-") (pintype "passive"))
      (node (ref "C40") (pin "1") (pinfunction "1_1") (pintype "passive"))
      (node (ref "C41") (pin "1") (pinfunction "1_1") (pintype "passive"))
      (node (ref "C44") (pin "1") (pinfunction "1_1") (pintype "passive"))
      (node (ref "C45") (pin "1") (pinfunction "1_1") (pintype "passive"))
      (node (ref "C46") (pin "1") (pinfunction "1_1") (pintype "passive"))
      (node (ref "C5") (pin "1") (pinfunction "1_1") (pintype "passive"))
      (node (ref "C6") (pin "1") (pinfunction "1_1") (pintype "passive"))
      (node (ref "C8") (pin "2") (pinfunction "2_2") (pintype "passive"))
      (node (ref "C9") (pin "2") (pinfunction "2_2") (pintype "passive"))
      (node (ref "DC1") (pin "1") (pinfunction "-VIN_1") (pintype "passive"))
      (node (ref "DC1") (pin "7") (pinfunction "COMM_7") (pintype "passive"))
      (node (ref "DOA") (pin "1") (pinfunction "1_1") (pintype "passive"))
      (node (ref "DOA") (pin "5") (pinfunction "5_5") (pintype "passive"))
      (node (ref "HYD-PRS-A") (pin "1") (pinfunction "1_1") (pintype "passive"))
      (node (ref "HYD-PRS-B") (pin "1") (pinfunction "1_1") (pintype "passive"))
      (node (ref "IC1") (pin "19") (pinfunction "VSS_19") (pintype "power_in"))
      (node (ref "IC1") (pin "8") (pinfunction "VSS_8") (pintype "power_in"))
      (node (ref "IC2") (pin "7") (pinfunction "VSS_7") (pintype "power_in"))
      (node (ref "IC3") (pin "7") (pinfunction "VSS_7") (pintype "power_in"))
      (node (ref "IC4") (pin "12") (pinfunction "+IN_12") (pintype "input"))
      (node (ref "IC5") (pin "11") (pinfunction "A_11") (pintype "input"))
      (node (ref "IC5") (pin "12") (pinfunction "X0_12") (pintype "bidirectional"))
      (node (ref "IC5") (pin "13") (pinfunction "X1_13") (pintype "bidirectional"))
      (node (ref "IC5") (pin "6") (pinfunction "INH_6") (pintype "input"))
      (node (ref "IC5") (pin "8") (pinfunction "GND_8") (pintype "power_in"))
      (node (ref "IC6") (pin "11") (pinfunction "A_11") (pintype "input"))
      (node (ref "IC6") (pin "12") (pinfunction "X0_12") (pintype "bidirectional"))
      (node (ref "IC6") (pin "13") (pinfunction "X1_13") (pintype "bidirectional"))
      (node (ref "IC6") (pin "6") (pinfunction "INH_6") (pintype "input"))
      (node (ref "IC6") (pin "8") (pinfunction "GND_8") (pintype "power_in"))
      (node (ref "IC7") (pin "10") (pinfunction "+IN_10") (pintype "input"))
      (node (ref "IC7") (pin "12") (pinfunction "+IN_12") (pintype "input"))
      (node (ref "IC7") (pin "3") (pinfunction "+IN_3") (pintype "input"))
      (node (ref "IC7") (pin "5") (pinfunction "+IN_5") (pintype "input"))
      (node (ref "IC9") (pin "8") (pinfunction "GND_8") (pintype "power_in"))
      (node (ref "P2") (pin "1") (pinfunction "A_1") (pintype "passive"))
      (node (ref "P3") (pin "1") (pinfunction "A_1") (pintype "passive"))
      (node (ref "P4") (pin "1") (pinfunction "A_1") (pintype "passive"))
      (node (ref "P5") (pin "1") (pinfunction "A_1") (pintype "passive"))
      (node (ref "P6") (pin "1") (pinfunction "A_1") (pintype "passive"))
      (node (ref "P7") (pin "1") (pinfunction "A_1") (pintype "passive"))
      (node (ref "POWER") (pin "2") (pinfunction "2_2") (pintype "passive"))
      (node (ref "POWER") (pin "4") (pinfunction "4_4") (pintype "passive"))
      (node (ref "R2") (pin "1") (pinfunction "1_1") (pintype "passive"))
      (node (ref "R27") (pin "2") (pinfunction "2_2") (pintype "passive"))
      (node (ref "R31") (pin "1") (pinfunction "1_1") (pintype "passive"))
      (node (ref "R32") (pin "2") (pinfunction "2_2") (pintype "passive"))
      (node (ref "R40") (pin "1") (pinfunction "1_1") (pintype "passive"))
      (node (ref "R45") (pin "1") (pinfunction "1_1") (pintype "passive"))
      (node (ref "R46") (pin "1") (pinfunction "1_1") (pintype "passive"))
      (node (ref "R51") (pin "1") (pinfunction "1_1") (pintype "passive"))
      (node (ref "R52") (pin "1") (pinfunction "1_1") (pintype "passive"))
      (node (ref "R57") (pin "1") (pinfunction "1_1") (pintype "passive"))
      (node (ref "U/D") (pin "1") (pinfunction "1_1") (pintype "passive"))
      (node (ref "USB") (pin "4") (pinfunction "4_4") (pintype "passive"))
      (node (ref "USB") (pin "S1") (pinfunction "S1_S1") (pintype "passive"))
      (node (ref "USB") (pin "S2") (pinfunction "S2_S2") (pintype "passive"))
    )
    (net (code "19") (name "LD2") (class "Default")
      (node (ref "IC1") (pin "12") (pinfunction "RC1/T1OSI/ICCP2/~{UOE}_12") (pintype "bidirectional"))
      (node (ref "IC2") (pin "5") (pinfunction "~{LDAC}_5") (pintype "input"))
    )
    (net (code "20") (name "LD3") (class "Default")
      (node (ref "IC1") (pin "17") (pinfunction "RC6/TX/CK_17") (pintype "bidirectional"))
      (node (ref "IC3") (pin "5") (pinfunction "~{LDAC}_5") (pintype "input"))
    )
    (net (code "21") (name "MCLR") (class "Default")
      (node (ref "DOA") (pin "3") (pinfunction "3_3") (pintype "passive"))
      (node (ref "IC1") (pin "1") (pinfunction "~{MCLR}/VPP/RE3_1") (pintype "input"))
      (node (ref "R5") (pin "1") (pinfunction "1_1") (pintype "passive"))
    )
    (net (code "22") (name "Net-(C7-Pad1)") (class "Default")
      (node (ref "C7") (pin "1") (pinfunction "1_1") (pintype "passive"))
      (node (ref "R11") (pin "1") (pinfunction "1_1") (pintype "passive"))
      (node (ref "R7") (pin "2") (pinfunction "2_2") (pintype "passive"))
    )
    (net (code "23") (name "Net-(C10-Pad1)") (class "Default")
      (node (ref "C10") (pin "1") (pinfunction "1_1") (pintype "passive"))
      (node (ref "R12") (pin "1") (pinfunction "1_1") (pintype "passive"))
      (node (ref "R13") (pin "2") (pinfunction "2_2") (pintype "passive"))
    )
    (net (code "24") (name "Net-(C11-Pad1)") (class "Default")
      (node (ref "C11") (pin "1") (pinfunction "1_1") (pintype "passive"))
      (node (ref "R6") (pin "2") (pinfunction "2_2") (pintype "passive"))
      (node (ref "R8") (pin "1") (pinfunction "1_1") (pintype "passive"))
    )
    (net (code "25") (name "Net-(C14-Pad1)") (class "Default")
      (node (ref "C14") (pin "1") (pinfunction "1_1") (pintype "passive"))
      (node (ref "R10") (pin "2") (pinfunction "2_2") (pintype "passive"))
      (node (ref "R9") (pin "1") (pinfunction "1_1") (pintype "passive"))
    )
    (net (code "26") (name "Net-(C17-Pad1)") (class "Default")
      (node (ref "C17") (pin "1") (pinfunction "1_1") (pintype "passive"))
      (node (ref "R19") (pin "1") (pinfunction "1_1") (pintype "passive"))
    )
    (net (code "27") (name "Net-(C18-Pad1)") (class "Default")
      (node (ref "C18") (pin "1") (pinfunction "1_1") (pintype "passive"))
      (node (ref "R21") (pin "1") (pinfunction "1_1") (pintype "passive"))
    )
    (net (code "28") (name "Net-(C21-Pad1)") (class "Default")
      (node (ref "C21") (pin "1") (pinfunction "1_1") (pintype "passive"))
      (node (ref "R23") (pin "1") (pinfunction "1_1") (pintype "passive"))
    )
    (net (code "29") (name "Net-(C22-Pad1)") (class "Default")
      (node (ref "C22") (pin "1") (pinfunction "1_1") (pintype "passive"))
      (node (ref "R25") (pin "1") (pinfunction "1_1") (pintype "passive"))
    )
    (net (code "30") (name "Net-(C23-Pad1)") (class "Default")
      (node (ref "C23") (pin "1") (pinfunction "1_1") (pintype "passive"))
      (node (ref "R30") (pin "2") (pinfunction "2_2") (pintype "passive"))
    )
    (net (code "31") (name "Net-(C34-Pad2)") (class "Default")
      (node (ref "C34") (pin "2") (pinfunction "2_2") (pintype "passive"))
      (node (ref "HYD-PRS-A") (pin "2") (pinfunction "2_2") (pintype "passive"))
      (node (ref "R41") (pin "2") (pinfunction "2_2") (pintype "passive"))
      (node (ref "T1") (pin "E") (pinfunction "E_E") (pintype "passive"))
      (node (ref "T2") (pin "E") (pinfunction "E_E") (pintype "passive"))
    )
    (net (code "32") (name "Net-(C35-Pad2)") (class "Default")
      (node (ref "C35") (pin "2") (pinfunction "2_2") (pintype "passive"))
      (node (ref "HYD-PRS-B") (pin "2") (pinfunction "2_2") (pintype "passive"))
      (node (ref "R44") (pin "2") (pinfunction "2_2") (pintype "passive"))
      (node (ref "T3") (pin "E") (pinfunction "E_E") (pintype "passive"))
      (node (ref "T4") (pin "E") (pinfunction "E_E") (pintype "passive"))
    )
    (net (code "33") (name "Net-(C38-Pad2)") (class "Default")
      (node (ref "C38") (pin "2") (pinfunction "2_2") (pintype "passive"))
      (node (ref "HYD-PRS-A") (pin "4") (pinfunction "4_4") (pintype "passive"))
      (node (ref "R47") (pin "2") (pinfunction "2_2") (pintype "passive"))
      (node (ref "T5") (pin "E") (pinfunction "E_E") (pintype "passive"))
      (node (ref "T6") (pin "E") (pinfunction "E_E") (pintype "passive"))
    )
    (net (code "34") (name "Net-(C39-Pad2)") (class "Default")
      (node (ref "C39") (pin "2") (pinfunction "2_2") (pintype "passive"))
      (node (ref "HYD-PRS-A") (pin "3") (pinfunction "3_3") (pintype "passive"))
      (node (ref "R50") (pin "2") (pinfunction "2_2") (pintype "passive"))
      (node (ref "T7") (pin "E") (pinfunction "E_E") (pintype "passive"))
      (node (ref "T8") (pin "E") (pinfunction "E_E") (pintype "passive"))
    )
    (net (code "35") (name "Net-(C42-Pad2)") (class "Default")
      (node (ref "C42") (pin "2") (pinfunction "2_2") (pintype "passive"))
      (node (ref "HYD-PRS-B") (pin "3") (pinfunction "3_3") (pintype "passive"))
      (node (ref "R53") (pin "2") (pinfunction "2_2") (pintype "passive"))
      (node (ref "T10") (pin "E") (pinfunction "E_E") (pintype "passive"))
      (node (ref "T9") (pin "E") (pinfunction "E_E") (pintype "passive"))
    )
    (net (code "36") (name "Net-(C43-Pad2)") (class "Default")
      (node (ref "C43") (pin "2") (pinfunction "2_2") (pintype "passive"))
      (node (ref "HYD-PRS-B") (pin "4") (pinfunction "4_4") (pintype "passive"))
      (node (ref "R56") (pin "2") (pinfunction "2_2") (pintype "passive"))
      (node (ref "T11") (pin "E") (pinfunction "E_E") (pintype "passive"))
      (node (ref "T12") (pin "E") (pinfunction "E_E") (pintype "passive"))
    )
    (net (code "37") (name "Net-(D1-PadC)") (class "Default")
      (node (ref "D1") (pin "C") (pinfunction "C_C") (pintype "passive"))
      (node (ref "D2") (pin "A") (pinfunction "A_A") (pintype "passive"))
      (node (ref "R34") (pin "2") (pinfunction "2_2") (pintype "passive"))
    )
    (net (code "38") (name "Net-(DIAG-C)") (class "Default")
      (node (ref "DIAG") (pin "K") (pinfunction "C_K") (pintype "passive"))
      (node (ref "R4") (pin "1") (pinfunction "1_1") (pintype "passive"))
    )
    (net (code "39") (name "Net-(IC1-OSC1{slash}CLKI)") (class "Default")
      (node (ref "C1") (pin "2") (pinfunction "2_2") (pintype "passive"))
      (node (ref "IC1") (pin "9") (pinfunction "OSC1/CLKI_9") (pintype "input"))
      (node (ref "Q1") (pin "2") (pinfunction "2_2") (pintype "passive"))
    )
    (net (code "40") (name "Net-(IC1-RA6{slash}OSC2{slash}CLKO)") (class "Default")
      (node (ref "C2") (pin "2") (pinfunction "2_2") (pintype "passive"))
      (node (ref "IC1") (pin "10") (pinfunction "RA6/OSC2/CLKO_10") (pintype "output"))
      (node (ref "Q1") (pin "1") (pinfunction "1_1") (pintype "passive"))
    )
    (net (code "41") (name "Net-(IC1-RC2{slash}CCP1{slash}P1A)") (class "Default")
      (node (ref "IC1") (pin "13") (pinfunction "RC2/CCP1/P1A_13") (pintype "bidirectional"))
      (node (ref "R1") (pin "2") (pinfunction "2_2") (pintype "passive"))
      (node (ref "R2") (pin "2") (pinfunction "2_2") (pintype "passive"))
    )
    (net (code "42") (name "Net-(IC1-VUSB)") (class "Default")
      (node (ref "C3") (pin "1") (pinfunction "1_1") (pintype "passive"))
      (node (ref "IC1") (pin "14") (pinfunction "VUSB_14") (pintype "bidirectional"))
    )
    (net (code "43") (name "Net-(IC4A-+IN)") (class "Default")
      (node (ref "IC4") (pin "3") (pinfunction "+IN_3") (pintype "input"))
      (node (ref "IC4") (pin "8") (pinfunction "OUT_8") (pintype "output"))
      (node (ref "IC5") (pin "1") (pinfunction "Y1_1") (pintype "bidirectional"))
      (node (ref "IC5") (pin "3") (pinfunction "Z1_3") (pintype "bidirectional"))
      (node (ref "IC6") (pin "1") (pinfunction "Y1_1") (pintype "bidirectional"))
      (node (ref "IC6") (pin "3") (pinfunction "Z1_3") (pintype "bidirectional"))
      (node (ref "R26") (pin "1") (pinfunction "1_1") (pintype "passive"))
      (node (ref "TP1") (pin "TP") (pinfunction "PP_TP") (pintype "input"))
    )
    (net (code "44") (name "Net-(IC4B-+IN)") (class "Default")
      (node (ref "C24") (pin "2") (pinfunction "2_2") (pintype "passive"))
      (node (ref "IC4") (pin "5") (pinfunction "+IN_5") (pintype "input"))
      (node (ref "R30") (pin "1") (pinfunction "1_1") (pintype "passive"))
      (node (ref "R31") (pin "2") (pinfunction "2_2") (pintype "passive"))
    )
    (net (code "45") (name "Net-(IC4B--IN)") (class "Default")
      (node (ref "D1") (pin "A") (pinfunction "A_A") (pintype "passive"))
      (node (ref "D2") (pin "C") (pinfunction "C_C") (pintype "passive"))
      (node (ref "IC4") (pin "6") (pinfunction "-IN_6") (pintype "input"))
      (node (ref "R32") (pin "1") (pinfunction "1_1") (pintype "passive"))
      (node (ref "R33") (pin "2") (pinfunction "2_2") (pintype "passive"))
    )
    (net (code "46") (name "Net-(IC4B-OUT)") (class "Default")
      (node (ref "C23") (pin "2") (pinfunction "2_2") (pintype "passive"))
      (node (ref "IC4") (pin "7") (pinfunction "OUT_7") (pintype "output"))
      (node (ref "R29") (pin "1") (pinfunction "1_1") (pintype "passive"))
      (node (ref "R33") (pin "1") (pinfunction "1_1") (pintype "passive"))
      (node (ref "R34") (pin "1") (pinfunction "1_1") (pintype "passive"))
      (node (ref "R35") (pin "1") (pinfunction "1_1") (pintype "passive"))
    )
    (net (code "47") (name "Net-(IC4C-+IN)") (class "Default")
      (node (ref "IC4") (pin "10") (pinfunction "+IN_10") (pintype "input"))
      (node (ref "R29") (pin "2") (pinfunction "2_2") (pintype "passive"))
    )
    (net (code "48") (name "Net-(IC4C--IN)") (class "Default")
      (node (ref "IC4") (pin "9") (pinfunction "-IN_9") (pintype "input"))
      (node (ref "R26") (pin "2") (pinfunction "2_2") (pintype "passive"))
      (node (ref "R27") (pin "1") (pinfunction "1_1") (pintype "passive"))
    )
    (net (code "49") (name "Net-(IC4D--IN)") (class "Default")
      (node (ref "IC4") (pin "13") (pinfunction "-IN_13") (pintype "input"))
      (node (ref "R28") (pin "2") (pinfunction "2_2") (pintype "passive"))
      (node (ref "R35") (pin "2") (pinfunction "2_2") (pintype "passive"))
    )
    (net (code "50") (name "Net-(IC4D-OUT)") (class "Default")
      (node (ref "IC4") (pin "14") (pinfunction "OUT_14") (pintype "output"))
      (node (ref "IC5") (pin "2") (pinfunction "Y0_2") (pintype "bidirectional"))
      (node (ref "IC5") (pin "5") (pinfunction "Z0_5") (pintype "bidirectional"))
      (node (ref "IC6") (pin "2") (pinfunction "Y0_2") (pintype "bidirectional"))
      (node (ref "IC6") (pin "5") (pinfunction "Z0_5") (pintype "bidirectional"))
      (node (ref "P1") (pin "2") (pinfunction "S_2") (pintype "passive"))
      (node (ref "P1") (pin "3") (pinfunction "E_3") (pintype "passive"))
      (node (ref "TP2") (pin "TP") (pinfunction "PP_TP") (pintype "input"))
    )
    (net (code "51") (name "Net-(IC7A--IN)") (class "Default")
      (node (ref "C30") (pin "1") (pinfunction "1_1") (pintype "passive"))
      (node (ref "IC7") (pin "2") (pinfunction "-IN_2") (pintype "input"))
      (node (ref "IC9") (pin "13") (pinfunction "OUT_13") (pintype "output"))
      (node (ref "R39") (pin "1") (pinfunction "1_1") (pintype "passive"))
    )
    (net (code "52") (name "Net-(IC7B--IN)") (class "Default")
      (node (ref "C28") (pin "1") (pinfunction "1_1") (pintype "passive"))
      (node (ref "IC7") (pin "6") (pinfunction "-IN_6") (pintype "input"))
      (node (ref "IC9") (pin "12") (pinfunction "OUT_12") (pintype "output"))
      (node (ref "R38") (pin "1") (pinfunction "1_1") (pintype "passive"))
    )
    (net (code "53") (name "Net-(IC7C--IN)") (class "Default")
      (node (ref "C27") (pin "1") (pinfunction "1_1") (pintype "passive"))
      (node (ref "IC7") (pin "9") (pinfunction "-IN_9") (pintype "input"))
      (node (ref "IC9") (pin "5") (pinfunction "OUT_5") (pintype "output"))
      (node (ref "R36") (pin "1") (pinfunction "1_1") (pintype "passive"))
    )
    (net (code "54") (name "Net-(IC7D--IN)") (class "Default")
      (node (ref "C29") (pin "1") (pinfunction "1_1") (pintype "passive"))
      (node (ref "IC7") (pin "13") (pinfunction "-IN_13") (pintype "input"))
      (node (ref "IC9") (pin "4") (pinfunction "OUT_4") (pintype "output"))
      (node (ref "R37") (pin "1") (pinfunction "1_1") (pintype "passive"))
    )
    (net (code "55") (name "Net-(IC8A-+IN)") (class "Default")
      (node (ref "C13") (pin "1") (pinfunction "1_1") (pintype "passive"))
      (node (ref "IC8") (pin "3") (pinfunction "+IN_3") (pintype "input"))
      (node (ref "R9") (pin "2") (pinfunction "2_2") (pintype "passive"))
    )
    (net (code "56") (name "Net-(IC8A--IN)") (class "Default")
      (node (ref "C14") (pin "2") (pinfunction "2_2") (pintype "passive"))
      (node (ref "IC8") (pin "1") (pinfunction "OUT_1") (pintype "output"))
      (node (ref "IC8") (pin "2") (pinfunction "-IN_2") (pintype "input"))
      (node (ref "R16") (pin "1") (pinfunction "1_1") (pintype "passive"))
    )
    (net (code "57") (name "Net-(IC8B-+IN)") (class "Default")
      (node (ref "C12") (pin "1") (pinfunction "1_1") (pintype "passive"))
      (node (ref "IC8") (pin "5") (pinfunction "+IN_5") (pintype "input"))
      (node (ref "R8") (pin "2") (pinfunction "2_2") (pintype "passive"))
    )
    (net (code "58") (name "Net-(IC8B--IN)") (class "Default")
      (node (ref "C11") (pin "2") (pinfunction "2_2") (pintype "passive"))
      (node (ref "IC8") (pin "6") (pinfunction "-IN_6") (pintype "input"))
      (node (ref "IC8") (pin "7") (pinfunction "OUT_7") (pintype "output"))
      (node (ref "R17") (pin "1") (pinfunction "1_1") (pintype "passive"))
    )
    (net (code "59") (name "Net-(IC8C-+IN)") (class "Default")
      (node (ref "C8") (pin "1") (pinfunction "1_1") (pintype "passive"))
      (node (ref "IC8") (pin "10") (pinfunction "+IN_10") (pintype "input"))
      (node (ref "R11") (pin "2") (pinfunction "2_2") (pintype "passive"))
    )
    (net (code "60") (name "Net-(IC8C--IN)") (class "Default")
      (node (ref "C7") (pin "2") (pinfunction "2_2") (pintype "passive"))
      (node (ref "IC8") (pin "8") (pinfunction "OUT_8") (pintype "output"))
      (node (ref "IC8") (pin "9") (pinfunction "-IN_9") (pintype "input"))
      (node (ref "R15") (pin "1") (pinfunction "1_1") (pintype "passive"))
    )
    (net (code "61") (name "Net-(IC8D-+IN)") (class "Default")
      (node (ref "C9") (pin "1") (pinfunction "1_1") (pintype "passive"))
      (node (ref "IC8") (pin "12") (pinfunction "+IN_12") (pintype "input"))
      (node (ref "R12") (pin "2") (pinfunction "2_2") (pintype "passive"))
    )
    (net (code "62") (name "Net-(IC8D--IN)") (class "Default")
      (node (ref "C10") (pin "2") (pinfunction "2_2") (pintype "passive"))
      (node (ref "IC8") (pin "13") (pinfunction "-IN_13") (pintype "input"))
      (node (ref "IC8") (pin "14") (pinfunction "OUT_14") (pintype "output"))
      (node (ref "R14") (pin "1") (pinfunction "1_1") (pintype "passive"))
    )
    (net (code "63") (name "Net-(IC9A-CTRL)") (class "Default")
      (node (ref "IC9") (pin "3") (pinfunction "CTRL_3") (pintype "input"))
      (node (ref "R17") (pin "2") (pinfunction "2_2") (pintype "passive"))
    )
    (net (code "64") (name "Net-(IC9A-IN)") (class "Default")
      (node (ref "IC9") (pin "2") (pinfunction "IN_2") (pintype "input"))
      (node (ref "R24") (pin "2") (pinfunction "2_2") (pintype "passive"))
      (node (ref "R25") (pin "2") (pinfunction "2_2") (pintype "passive"))
    )
    (net (code "65") (name "Net-(IC9B-CTRL)") (class "Default")
      (node (ref "IC9") (pin "6") (pinfunction "CTRL_6") (pintype "input"))
      (node (ref "R16") (pin "2") (pinfunction "2_2") (pintype "passive"))
    )
    (net (code "66") (name "Net-(IC9B-IN)") (class "Default")
      (node (ref "IC9") (pin "7") (pinfunction "IN_7") (pintype "input"))
      (node (ref "R22") (pin "2") (pinfunction "2_2") (pintype "passive"))
      (node (ref "R23") (pin "2") (pinfunction "2_2") (pintype "passive"))
    )
    (net (code "67") (name "Net-(IC9C-CTRL)") (class "Default")
      (node (ref "IC9") (pin "11") (pinfunction "CTRL_11") (pintype "input"))
      (node (ref "R14") (pin "2") (pinfunction "2_2") (pintype "passive"))
    )
    (net (code "68") (name "Net-(IC9C-IN)") (class "Default")
      (node (ref "IC9") (pin "10") (pinfunction "IN_10") (pintype "input"))
      (node (ref "R20") (pin "2") (pinfunction "2_2") (pintype "passive"))
      (node (ref "R21") (pin "2") (pinfunction "2_2") (pintype "passive"))
    )
    (net (code "69") (name "Net-(IC9D-CTRL)") (class "Default")
      (node (ref "IC9") (pin "14") (pinfunction "CTRL_14") (pintype "input"))
      (node (ref "R15") (pin "2") (pinfunction "2_2") (pintype "passive"))
    )
    (net (code "70") (name "Net-(IC9D-IN)") (class "Default")
      (node (ref "IC9") (pin "15") (pinfunction "IN_15") (pintype "input"))
      (node (ref "R18") (pin "2") (pinfunction "2_2") (pintype "passive"))
      (node (ref "R19") (pin "2") (pinfunction "2_2") (pintype "passive"))
    )
    (net (code "71") (name "Net-(IC10A-+IN)") (class "Default")
      (node (ref "IC10") (pin "3") (pinfunction "+IN_3") (pintype "input"))
      (node (ref "R43") (pin "2") (pinfunction "2_2") (pintype "passive"))
    )
    (net (code "72") (name "Net-(IC10A--IN)") (class "Default")
      (node (ref "C35") (pin "1") (pinfunction "1_1") (pintype "passive"))
      (node (ref "C36") (pin "2") (pinfunction "2_2") (pintype "passive"))
      (node (ref "IC10") (pin "2") (pinfunction "-IN_2") (pintype "input"))
      (node (ref "R44") (pin "1") (pinfunction "1_1") (pintype "passive"))
      (node (ref "R45") (pin "2") (pinfunction "2_2") (pintype "passive"))
    )
    (net (code "73") (name "Net-(IC10A-OUT)") (class "Default")
      (node (ref "IC10") (pin "1") (pinfunction "OUT_1") (pintype "output"))
      (node (ref "R60") (pin "1") (pinfunction "1_1") (pintype "passive"))
      (node (ref "R61") (pin "1") (pinfunction "1_1") (pintype "passive"))
    )
    (net (code "74") (name "Net-(IC10B-+IN)") (class "Default")
      (node (ref "IC10") (pin "5") (pinfunction "+IN_5") (pintype "input"))
      (node (ref "R42") (pin "2") (pinfunction "2_2") (pintype "passive"))
    )
    (net (code "75") (name "Net-(IC10B--IN)") (class "Default")
      (node (ref "C33") (pin "2") (pinfunction "2_2") (pintype "passive"))
      (node (ref "C34") (pin "1") (pinfunction "1_1") (pintype "passive"))
      (node (ref "IC10") (pin "6") (pinfunction "-IN_6") (pintype "input"))
      (node (ref "R40") (pin "2") (pinfunction "2_2") (pintype "passive"))
      (node (ref "R41") (pin "1") (pinfunction "1_1") (pintype "passive"))
    )
    (net (code "76") (name "Net-(IC10B-OUT)") (class "Default")
      (node (ref "IC10") (pin "7") (pinfunction "OUT_7") (pintype "output"))
      (node (ref "R58") (pin "1") (pinfunction "1_1") (pintype "passive"))
      (node (ref "R59") (pin "1") (pinfunction "1_1") (pintype "passive"))
    )
    (net (code "77") (name "Net-(IC11A-+IN)") (class "Default")
      (node (ref "IC11") (pin "3") (pinfunction "+IN_3") (pintype "input"))
      (node (ref "R49") (pin "2") (pinfunction "2_2") (pintype "passive"))
    )
    (net (code "78") (name "Net-(IC11A--IN)") (class "Default")
      (node (ref "C39") (pin "1") (pinfunction "1_1") (pintype "passive"))
      (node (ref "C40") (pin "2") (pinfunction "2_2") (pintype "passive"))
      (node (ref "IC11") (pin "2") (pinfunction "-IN_2") (pintype "input"))
      (node (ref "R50") (pin "1") (pinfunction "1_1") (pintype "passive"))
      (node (ref "R51") (pin "2") (pinfunction "2_2") (pintype "passive"))
    )
    (net (code "79") (name "Net-(IC11A-OUT)") (class "Default")
      (node (ref "IC11") (pin "1") (pinfunction "OUT_1") (pintype "output"))
      (node (ref "R64") (pin "1") (pinfunction "1_1") (pintype "passive"))
      (node (ref "R65") (pin "1") (pinfunction "1_1") (pintype "passive"))
    )
    (net (code "80") (name "Net-(IC11B-+IN)") (class "Default")
      (node (ref "IC11") (pin "5") (pinfunction "+IN_5") (pintype "input"))
      (node (ref "R48") (pin "2") (pinfunction "2_2") (pintype "passive"))
    )
    (net (code "81") (name "Net-(IC11B--IN)") (class "Default")
      (node (ref "C37") (pin "2") (pinfunction "2_2") (pintype "passive"))
      (node (ref "C38") (pin "1") (pinfunction "1_1") (pintype "passive"))
      (node (ref "IC11") (pin "6") (pinfunction "-IN_6") (pintype "input"))
      (node (ref "R46") (pin "2") (pinfunction "2_2") (pintype "passive"))
      (node (ref "R47") (pin "1") (pinfunction "1_1") (pintype "passive"))
    )
    (net (code "82") (name "Net-(IC11B-OUT)") (class "Default")
      (node (ref "IC11") (pin "7") (pinfunction "OUT_7") (pintype "output"))
      (node (ref "R62") (pin "1") (pinfunction "1_1") (pintype "passive"))
      (node (ref "R63") (pin "1") (pinfunction "1_1") (pintype "passive"))
    )
    (net (code "83") (name "Net-(IC12A-+IN)") (class "Default")
      (node (ref "IC12") (pin "3") (pinfunction "+IN_3") (pintype "input"))
      (node (ref "R55") (pin "2") (pinfunction "2_2") (pintype "passive"))
    )
    (net (code "84") (name "Net-(IC12A--IN)") (class "Default")
      (node (ref "C43") (pin "1") (pinfunction "1_1") (pintype "passive"))
      (node (ref "C44") (pin "2") (pinfunction "2_2") (pintype "passive"))
      (node (ref "IC12") (pin "2") (pinfunction "-IN_2") (pintype "input"))
      (node (ref "R56") (pin "1") (pinfunction "1_1") (pintype "passive"))
      (node (ref "R57") (pin "2") (pinfunction "2_2") (pintype "passive"))
    )
    (net (code "85") (name "Net-(IC12A-OUT)") (class "Default")
      (node (ref "IC12") (pin "1") (pinfunction "OUT_1") (pintype "output"))
      (node (ref "R68") (pin "1") (pinfunction "1_1") (pintype "passive"))
      (node (ref "R69") (pin "1") (pinfunction "1_1") (pintype "passive"))
    )
    (net (code "86") (name "Net-(IC12B-+IN)") (class "Default")
      (node (ref "IC12") (pin "5") (pinfunction "+IN_5") (pintype "input"))
      (node (ref "R54") (pin "2") (pinfunction "2_2") (pintype "passive"))
    )
    (net (code "87") (name "Net-(IC12B--IN)") (class "Default")
      (node (ref "C41") (pin "2") (pinfunction "2_2") (pintype "passive"))
      (node (ref "C42") (pin "1") (pinfunction "1_1") (pintype "passive"))
      (node (ref "IC12") (pin "6") (pinfunction "-IN_6") (pintype "input"))
      (node (ref "R52") (pin "2") (pinfunction "2_2") (pintype "passive"))
      (node (ref "R53") (pin "1") (pinfunction "1_1") (pintype "passive"))
    )
    (net (code "88") (name "Net-(IC12B-OUT)") (class "Default")
      (node (ref "IC12") (pin "7") (pinfunction "OUT_7") (pintype "output"))
      (node (ref "R66") (pin "1") (pinfunction "1_1") (pintype "passive"))
      (node (ref "R67") (pin "1") (pinfunction "1_1") (pintype "passive"))
    )
    (net (code "89") (name "Net-(P1-A)") (class "Default")
      (node (ref "P1") (pin "1") (pinfunction "A_1") (pintype "passive"))
      (node (ref "R28") (pin "1") (pinfunction "1_1") (pintype "passive"))
    )
    (net (code "90") (name "Net-(P2-S)") (class "Default")
      (node (ref "P2") (pin "2") (pinfunction "S_2") (pintype "passive"))
      (node (ref "R42") (pin "1") (pinfunction "1_1") (pintype "passive"))
    )
    (net (code "91") (name "Net-(P3-S)") (class "Default")
      (node (ref "P3") (pin "2") (pinfunction "S_2") (pintype "passive"))
      (node (ref "R43") (pin "1") (pinfunction "1_1") (pintype "passive"))
    )
    (net (code "92") (name "Net-(P4-S)") (class "Default")
      (node (ref "P4") (pin "2") (pinfunction "S_2") (pintype "passive"))
      (node (ref "R48") (pin "1") (pinfunction "1_1") (pintype "passive"))
    )
    (net (code "93") (name "Net-(P5-S)") (class "Default")
      (node (ref "P5") (pin "2") (pinfunction "S_2") (pintype "passive"))
      (node (ref "R49") (pin "1") (pinfunction "1_1") (pintype "passive"))
    )
    (net (code "94") (name "Net-(P6-S)") (class "Default")
      (node (ref "P6") (pin "2") (pinfunction "S_2") (pintype "passive"))
      (node (ref "R54") (pin "1") (pinfunction "1_1") (pintype "passive"))
    )
    (net (code "95") (name "Net-(P7-S)") (class "Default")
      (node (ref "P7") (pin "2") (pinfunction "S_2") (pintype "passive"))
      (node (ref "R55") (pin "1") (pinfunction "1_1") (pintype "passive"))
    )
    (net (code "96") (name "Net-(R1-Pad1)") (class "Default")
      (node (ref "R1") (pin "1") (pinfunction "1_1") (pintype "passive"))
      (node (ref "USB") (pin "1") (pinfunction "1_1") (pintype "passive"))
    )
    (net (code "97") (name "Net-(R58-Pad2)") (class "Default")
      (node (ref "R58") (pin "2") (pinfunction "2_2") (pintype "passive"))
      (node (ref "T1") (pin "B") (pinfunction "B_B") (pintype "passive"))
    )
    (net (code "98") (name "Net-(R59-Pad2)") (class "Default")
      (node (ref "R59") (pin "2") (pinfunction "2_2") (pintype "passive"))
      (node (ref "T2") (pin "B") (pinfunction "B_B") (pintype "passive"))
    )
    (net (code "99") (name "Net-(R60-Pad2)") (class "Default")
      (node (ref "R60") (pin "2") (pinfunction "2_2") (pintype "passive"))
      (node (ref "T3") (pin "B") (pinfunction "B_B") (pintype "passive"))
    )
    (net (code "100") (name "Net-(R61-Pad2)") (class "Default")
      (node (ref "R61") (pin "2") (pinfunction "2_2") (pintype "passive"))
      (node (ref "T4") (pin "B") (pinfunction "B_B") (pintype "passive"))
    )
    (net (code "101") (name "Net-(R62-Pad2)") (class "Default")
      (node (ref "R62") (pin "2") (pinfunction "2_2") (pintype "passive"))
      (node (ref "T5") (pin "B") (pinfunction "B_B") (pintype "passive"))
    )
    (net (code "102") (name "Net-(R63-Pad2)") (class "Default")
      (node (ref "R63") (pin "2") (pinfunction "2_2") (pintype "passive"))
      (node (ref "T6") (pin "B") (pinfunction "B_B") (pintype "passive"))
    )
    (net (code "103") (name "Net-(R64-Pad2)") (class "Default")
      (node (ref "R64") (pin "2") (pinfunction "2_2") (pintype "passive"))
      (node (ref "T7") (pin "B") (pinfunction "B_B") (pintype "passive"))
    )
    (net (code "104") (name "Net-(R65-Pad2)") (class "Default")
      (node (ref "R65") (pin "2") (pinfunction "2_2") (pintype "passive"))
      (node (ref "T8") (pin "B") (pinfunction "B_B") (pintype "passive"))
    )
    (net (code "105") (name "Net-(R66-Pad2)") (class "Default")
      (node (ref "R66") (pin "2") (pinfunction "2_2") (pintype "passive"))
      (node (ref "T9") (pin "B") (pinfunction "B_B") (pintype "passive"))
    )
    (net (code "106") (name "Net-(R67-Pad2)") (class "Default")
      (node (ref "R67") (pin "2") (pinfunction "2_2") (pintype "passive"))
      (node (ref "T10") (pin "B") (pinfunction "B_B") (pintype "passive"))
    )
    (net (code "107") (name "Net-(R68-Pad2)") (class "Default")
      (node (ref "R68") (pin "2") (pinfunction "2_2") (pintype "passive"))
      (node (ref "T11") (pin "B") (pinfunction "B_B") (pintype "passive"))
    )
    (net (code "108") (name "Net-(R69-Pad2)") (class "Default")
      (node (ref "R69") (pin "2") (pinfunction "2_2") (pintype "passive"))
      (node (ref "T12") (pin "B") (pinfunction "B_B") (pintype "passive"))
    )
    (net (code "109") (name "S1A") (class "Default")
      (node (ref "IC5") (pin "4") (pinfunction "Z_4") (pintype "bidirectional"))
      (node (ref "R24") (pin "1") (pinfunction "1_1") (pintype "passive"))
    )
    (net (code "110") (name "S1B") (class "Default")
      (node (ref "IC6") (pin "4") (pinfunction "Z_4") (pintype "bidirectional"))
      (node (ref "R22") (pin "1") (pinfunction "1_1") (pintype "passive"))
    )
    (net (code "111") (name "S3A") (class "Default")
      (node (ref "IC5") (pin "15") (pinfunction "Y_15") (pintype "bidirectional"))
      (node (ref "R18") (pin "1") (pinfunction "1_1") (pintype "passive"))
    )
    (net (code "112") (name "S3B") (class "Default")
      (node (ref "IC6") (pin "15") (pinfunction "Y_15") (pintype "bidirectional"))
      (node (ref "R20") (pin "1") (pinfunction "1_1") (pintype "passive"))
    )
    (net (code "113") (name "SINROT") (class "Default")
      (node (ref "IC4") (pin "1") (pinfunction "OUT_1") (pintype "output"))
      (node (ref "IC4") (pin "2") (pinfunction "-IN_2") (pintype "input"))
      (node (ref "P2") (pin "3") (pinfunction "E_3") (pintype "passive"))
      (node (ref "P3") (pin "3") (pinfunction "E_3") (pintype "passive"))
    )
    (net (code "114") (name "SPI_CLK") (class "Default")
      (node (ref "IC1") (pin "22") (pinfunction "RB1/AN10/INT1/SCK/SCL_22") (pintype "bidirectional"))
      (node (ref "IC2") (pin "3") (pinfunction "SCK_3") (pintype "input"))
      (node (ref "IC3") (pin "3") (pinfunction "SCK_3") (pintype "input"))
    )
    (net (code "115") (name "SPI_DAT") (class "Default")
      (node (ref "IC1") (pin "18") (pinfunction "RC7/RX/DT/SDO_18") (pintype "bidirectional"))
      (node (ref "IC2") (pin "4") (pinfunction "SDI_4") (pintype "input"))
      (node (ref "IC3") (pin "4") (pinfunction "SDI_4") (pintype "input"))
    )
    (net (code "116") (name "SYNAS1POL") (class "Default")
      (node (ref "IC1") (pin "27") (pinfunction "RB6/KBI2/PGC_27") (pintype "bidirectional"))
      (node (ref "IC5") (pin "9") (pinfunction "C_9") (pintype "input"))
    )
    (net (code "117") (name "SYNAS3POL") (class "Default")
      (node (ref "IC1") (pin "26") (pinfunction "RB5/KBI1/PGM_26") (pintype "bidirectional"))
      (node (ref "IC5") (pin "10") (pinfunction "B_10") (pintype "input"))
    )
    (net (code "118") (name "SYNBS1POL") (class "Default")
      (node (ref "IC1") (pin "25") (pinfunction "RB4/AN11/KBI0/CSSPP_25") (pintype "bidirectional"))
      (node (ref "IC6") (pin "9") (pinfunction "C_9") (pintype "input"))
    )
    (net (code "119") (name "SYNBS3POL") (class "Default")
      (node (ref "IC1") (pin "24") (pinfunction "RB3/AN9/CCP2/VPO_24") (pintype "bidirectional"))
      (node (ref "IC6") (pin "10") (pinfunction "B_10") (pintype "input"))
    )
    (net (code "120") (name "USBDOA") (class "Default")
      (node (ref "IC1") (pin "2") (pinfunction "RA0/AN0_2") (pintype "bidirectional"))
      (node (ref "R3") (pin "1") (pinfunction "1_1") (pintype "passive"))
      (node (ref "U/D") (pin "2") (pinfunction "2_2") (pintype "passive"))
    )
    (net (code "121") (name "USB_DM") (class "Default")
      (node (ref "IC1") (pin "15") (pinfunction "RC4/D-/VM_15") (pintype "bidirectional"))
      (node (ref "USB") (pin "2") (pinfunction "2_2") (pintype "passive"))
    )
    (net (code "122") (name "USB_DP") (class "Default")
      (node (ref "IC1") (pin "16") (pinfunction "RC5/D+/VP_16") (pintype "bidirectional"))
      (node (ref "USB") (pin "3") (pinfunction "3_3") (pintype "passive"))
    )
    (net (code "123") (name "unconnected-(DC1-ON{slash}OFF-Pad3)") (class "Default")
      (node (ref "DC1") (pin "3") (pinfunction "ON/OFF_3") (pintype "passive"))
    )
    (net (code "124") (name "unconnected-(IC1-RA1{slash}AN1-Pad3)") (class "Default")
      (node (ref "IC1") (pin "3") (pinfunction "RA1/AN1_3") (pintype "bidirectional"))
    )
    (net (code "125") (name "unconnected-(IC1-RA5{slash}AN4{slash}~{SS}{slash}HLVDIN{slash}C2OUT-Pad7)") (class "Default")
      (node (ref "IC1") (pin "7") (pinfunction "RA5/AN4/~{SS}/HLVDIN/C2OUT_7") (pintype "bidirectional"))
    )
    (net (code "126") (name "unconnected-(IC1-RB0{slash}AN12{slash}INT0{slash}LFT0{slash}SDI{slash}SDA-Pad21)") (class "Default")
      (node (ref "IC1") (pin "21") (pinfunction "RB0/AN12/INT0/LFT0/SDI/SDA_21") (pintype "bidirectional"))
    )
    (net (code "127") (name "unconnected-(IC1-RB7{slash}BKI3{slash}PGD-Pad28)") (class "Default")
      (node (ref "IC1") (pin "28") (pinfunction "RB7/BKI3/PGD_28") (pintype "bidirectional"))
    )
    (net (code "128") (name "unconnected-(IC5A-X-Pad14)") (class "Default")
      (node (ref "IC5") (pin "14") (pinfunction "X_14") (pintype "bidirectional"))
    )
    (net (code "129") (name "unconnected-(IC6A-X-Pad14)") (class "Default")
      (node (ref "IC6") (pin "14") (pinfunction "X_14") (pintype "bidirectional"))
    )
    (net (code "130") (name "unconnected-(IC9E-MODE-Pad1)") (class "Default")
      (node (ref "IC9") (pin "1") (pinfunction "MODE_1") (pintype "input"))
    )
  )
)
